# Micromouse.net
KiCad netlist of a schematic drawn in Altium Designer
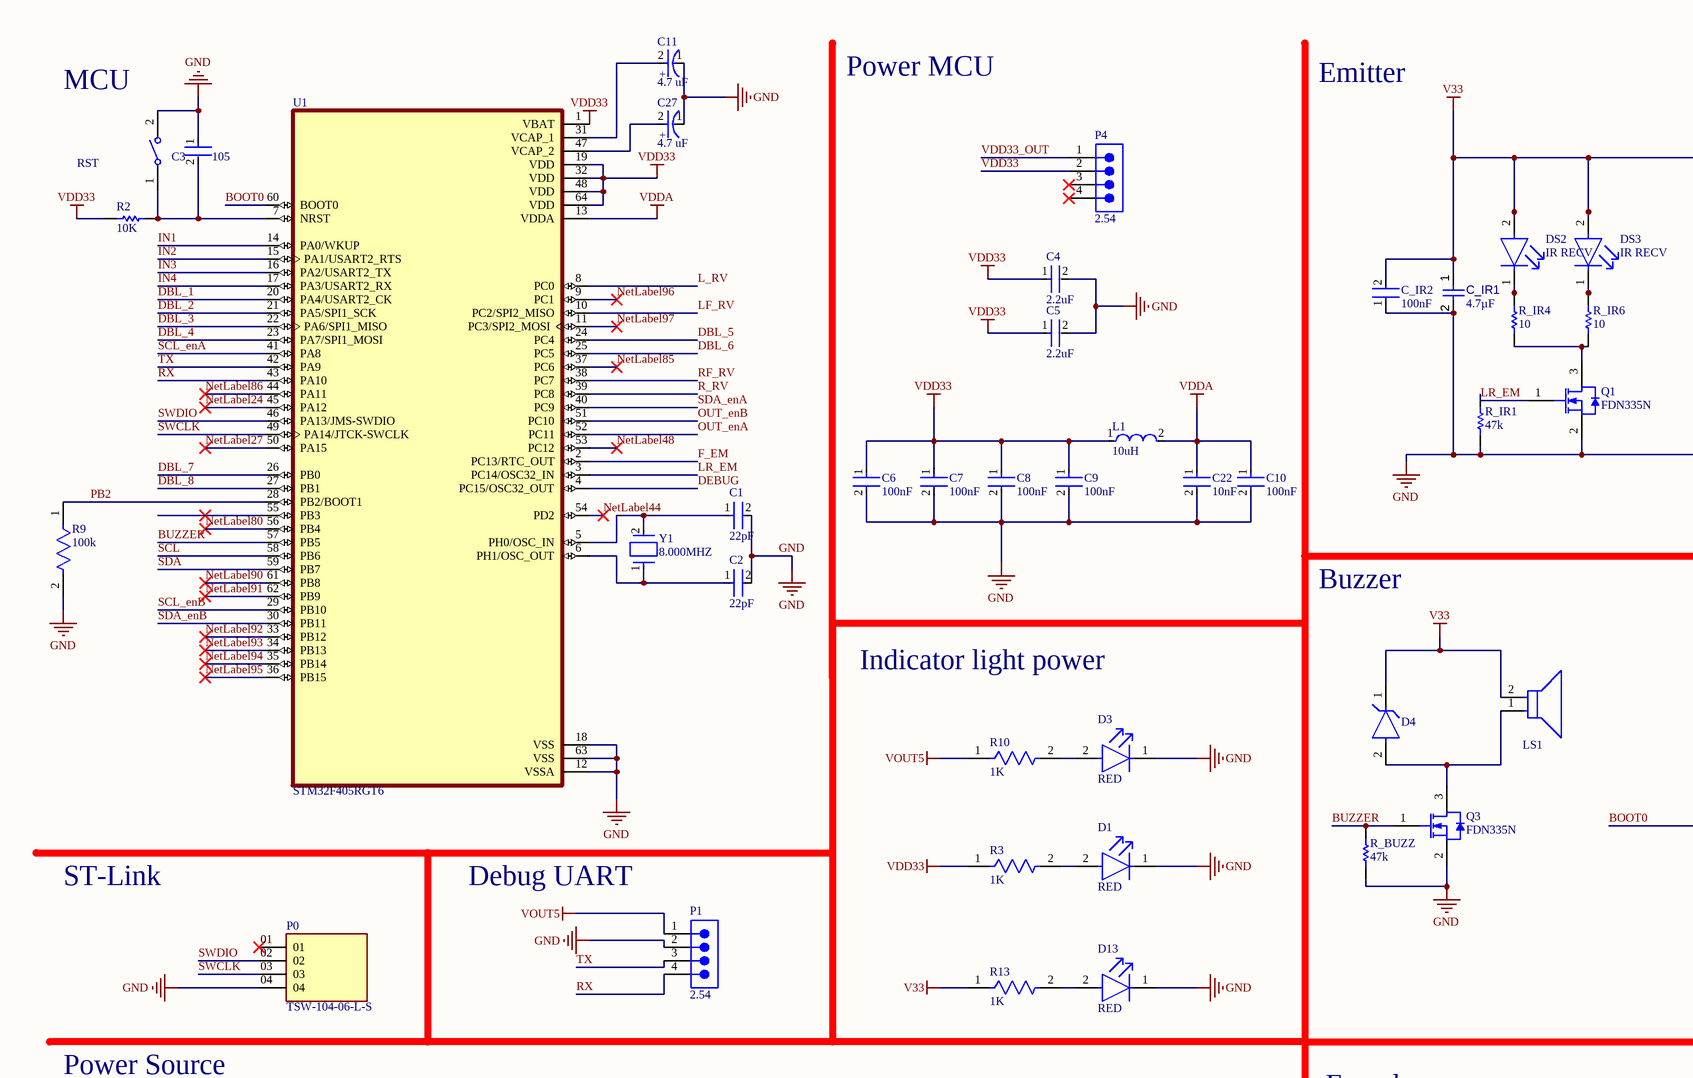
[diagram p0: Micromouse.SchDoc, top left]
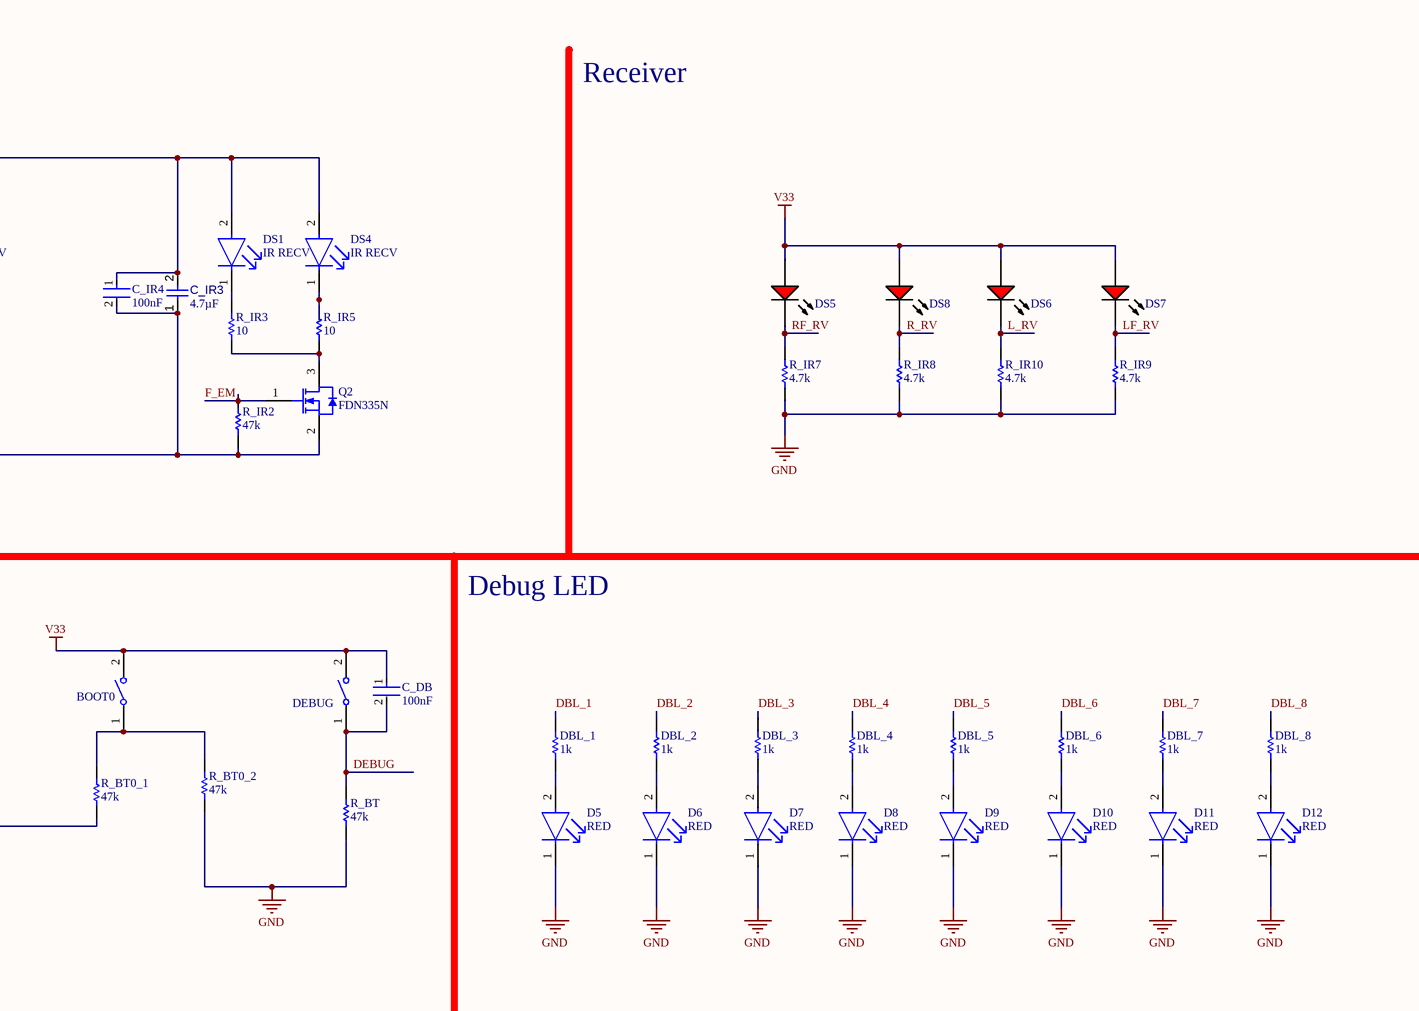
[diagram p1: Micromouse.SchDoc, top right]
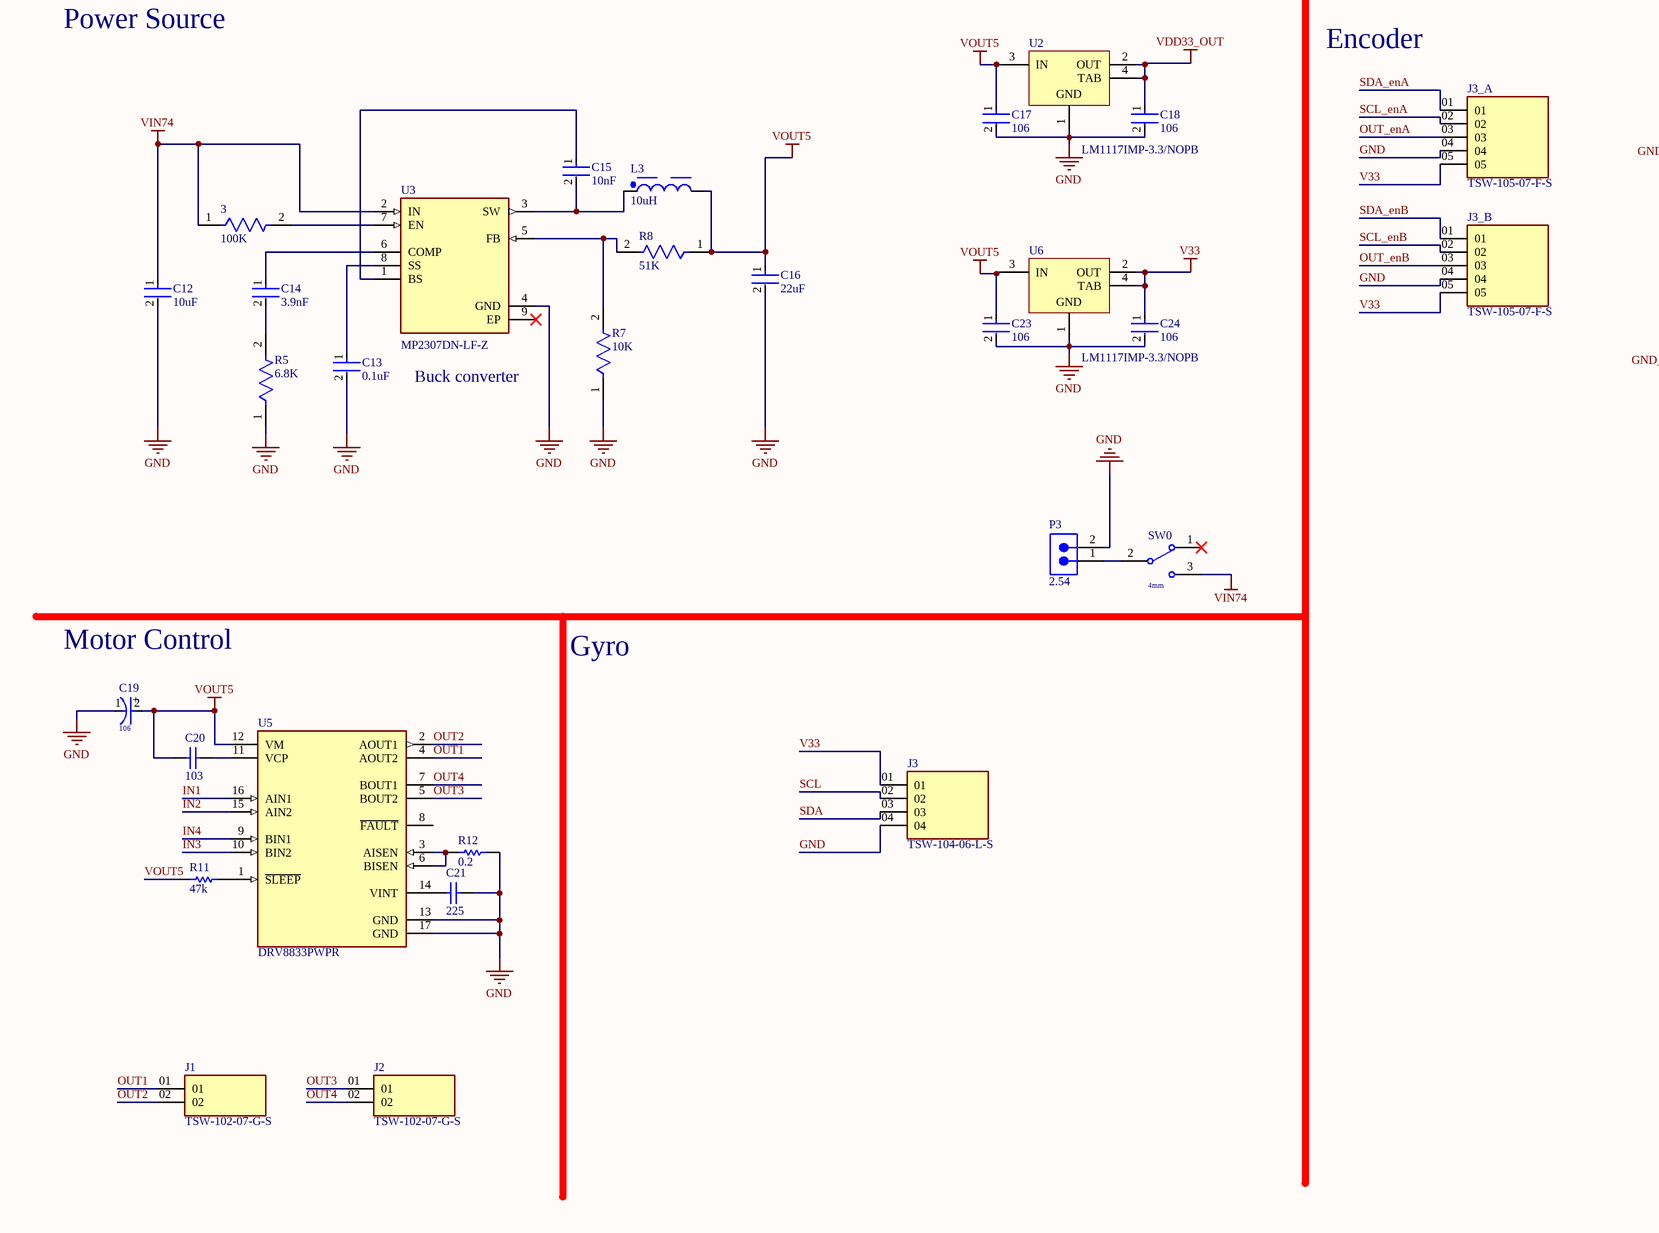
[diagram p2: Micromouse.SchDoc, bottom left]
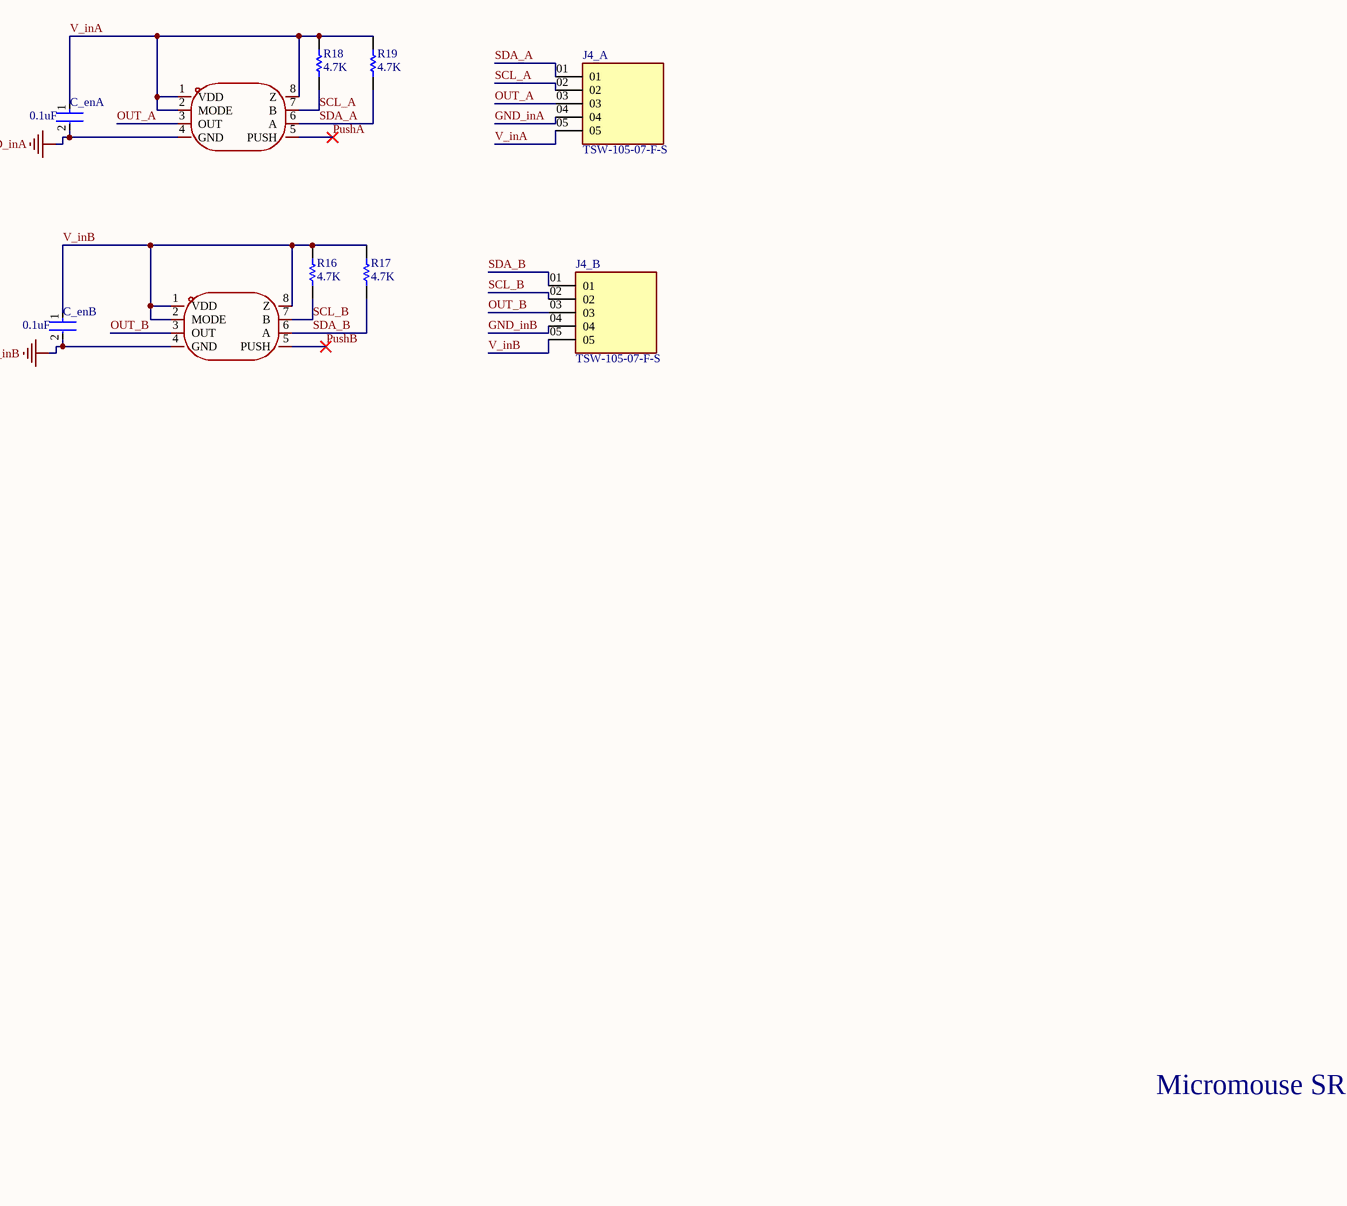
[diagram p3: Micromouse.SchDoc, bottom right]

(export (version "E")
  (design (tool "Eeschema 10.0.6"))
  (components
    (comp (ref "3")
      (value "100K")
      (footprint "FP-CRCW0805-e3-IPC_B")
      (description "RES Thick Film, 2.49Ω, 1%, 0.125W, 200ppm/°C, 0805")
      (fields (field (name "TOLERANCE") "1%"))
      (libsource (lib "Altium Content Vault") (part "1029c3af85768c4190bb7ad29bc67b5"))
    )
    (comp (ref "BOOT0")
      (value "~")
      (footprint "TECO-FSMSMTR_V")
      (description "FSMSM Push Button Switch, 50 mA, -35 to 85 degC, 2-Pin SMD, RoHS, Tape and Reel")
      (fields (field (name "MANUFACTURER") "TE Connectivity"))
      (libsource (lib "Altium Content Vault") (part "SW-SPST-2_C"))
    )
    (comp (ref "C1")
      (value "22pF")
      (footprint "FP-CL32-IPC_B")
      (description "Cap Ceramic 22uF 6.3V X7R ±20% SMD 1210 +125°C Embossed T/R")
      (fields (field (name "TOLERANCE") "20%"))
      (libsource (lib "Altium Content Vault") (part "b4654b650e69147ec39a6b967a45e02"))
    )
    (comp (ref "C2")
      (value "22pF")
      (footprint "FP-CL32-IPC_B")
      (description "Cap Ceramic 22uF 6.3V X7R ±20% SMD 1210 +125°C Embossed T/R")
      (fields (field (name "TOLERANCE") "20%"))
      (libsource (lib "Altium Content Vault") (part "b4654b650e69147ec39a6b967a45e02"))
    )
    (comp (ref "C3")
      (value "105")
      (footprint "FP-CL21-IPC_B")
      (description "CL21 Series 0805 1uF 25V -20/+80% Tolerance Y5V Multilayer Ceramic Chip Capacitor")
      (fields (field (name "TOLERANCE") "80%"))
      (libsource (lib "Altium Content Vault") (part "b4654b650e69147ec39a6b967a45e02"))
    )
    (comp (ref "C4")
      (value "2.2uF")
      (footprint "FP-CL21-IPC_B")
      (description "CL21 Series 0805 2.2uF 16V -20/+80% Tolerance Y5V Multilayer Ceramic Chip Capacitor")
      (fields (field (name "TOLERANCE") "80%") (field (name "VOLTAGE") "10V"))
      (libsource (lib "Altium Content Vault") (part "b4654b650e69147ec39a6b967a45e02"))
    )
    (comp (ref "C5")
      (value "2.2uF")
      (footprint "FP-CL21-IPC_B")
      (description "CL21 Series 0805 2.2uF 16V -20/+80% Tolerance Y5V Multilayer Ceramic Chip Capacitor")
      (fields (field (name "TOLERANCE") "80%") (field (name "VOLTAGE") "10V"))
      (libsource (lib "Altium Content Vault") (part "b4654b650e69147ec39a6b967a45e02"))
    )
    (comp (ref "C6")
      (value "100nF")
      (footprint "FP-CL10-IPC_C")
      (description "Cap Ceramic 100nF 25V X7R ±10% Pad SMD 0603 +125°C T/R")
      (fields (field (name "TOLERANCE") "10%"))
      (libsource (lib "Altium Content Vault") (part "b4654b650e69147ec39a6b967a45e02"))
    )
    (comp (ref "C7")
      (value "100nF")
      (footprint "FP-CL10-IPC_C")
      (description "Cap Ceramic 100nF 25V X7R ±10% Pad SMD 0603 +125°C T/R")
      (fields (field (name "TOLERANCE") "10%"))
      (libsource (lib "Altium Content Vault") (part "b4654b650e69147ec39a6b967a45e02"))
    )
    (comp (ref "C8")
      (value "100nF")
      (footprint "FP-CL10-IPC_C")
      (description "Cap Ceramic 100nF 25V X7R ±10% Pad SMD 0603 +125°C T/R")
      (fields (field (name "TOLERANCE") "10%"))
      (libsource (lib "Altium Content Vault") (part "b4654b650e69147ec39a6b967a45e02"))
    )
    (comp (ref "C9")
      (value "100nF")
      (footprint "FP-CL10-IPC_C")
      (description "Cap Ceramic 100nF 25V X7R ±10% Pad SMD 0603 +125°C T/R")
      (fields (field (name "TOLERANCE") "10%"))
      (libsource (lib "Altium Content Vault") (part "b4654b650e69147ec39a6b967a45e02"))
    )
    (comp (ref "C10")
      (value "100nF")
      (footprint "FP-CL10-IPC_C")
      (description "Cap Ceramic 100nF 25V X7R ±10% Pad SMD 0603 +125°C T/R")
      (fields (field (name "TOLERANCE") "10%"))
      (libsource (lib "Altium Content Vault") (part "b4654b650e69147ec39a6b967a45e02"))
    )
    (comp (ref "C11")
      (value "4.7 uF")
      (footprint "FP-TAJA-MFG")
      (description "4.7uF 20V  ±10% 4Ω 3216(mm)  SMD Tantalum Capacitor")
      (fields (field (name "TOLERANCE") "10%") (field (name "VOLTAGE") "20V"))
      (libsource (lib "Altium Content Vault") (part "203bc49f2ac43e59fd269a8c329ed05"))
    )
    (comp (ref "C12")
      (value "10uF")
      (footprint "FP-C1206C-EB-MFG")
      (description "C1206 10 uF C0G 5.00% 50 V")
      (fields
        (field (name "MANUFACTURER PART NUMBER") "C1206C100J5GAC")
        (field (name "MANUFACTURER") "KEMET")
      )
      (libsource (lib "Altium Content Vault") (part "b4654b650e69147ec39a6b967a45e02"))
    )
    (comp (ref "C13")
      (value "0.1uF")
      (footprint "FP-C1206C-EB-MFG")
      (description "C1206 10 pF C0G 5.00% 50 V")
      (fields
        (field (name "MANUFACTURER PART NUMBER") "C1206C100J5GAC")
        (field (name "MANUFACTURER") "KEMET")
      )
      (libsource (lib "Altium Content Vault") (part "b4654b650e69147ec39a6b967a45e02"))
    )
    (comp (ref "C14")
      (value "3.9nF")
      (footprint "FP-C1206C-EB-MFG")
      (description "C1206 4.8nF C0G 5.00% 50 V")
      (fields
        (field (name "MANUFACTURER PART NUMBER") "C1206C100J5GAC")
        (field (name "MANUFACTURER") "KEMET")
      )
      (libsource (lib "Altium Content Vault") (part "b4654b650e69147ec39a6b967a45e02"))
    )
    (comp (ref "C15")
      (value "10nF")
      (footprint "FP-C1206C-EB-MFG")
      (description "C1206 10 pF C0G 5.00% 50 V")
      (fields
        (field (name "MANUFACTURER PART NUMBER") "C1206C100J5GAC")
        (field (name "MANUFACTURER") "KEMET")
      )
      (libsource (lib "Altium Content Vault") (part "b4654b650e69147ec39a6b967a45e02"))
    )
    (comp (ref "C16")
      (value "22uF")
      (footprint "FP-C1206C-EB-MFG")
      (description "C1206 10 pF C0G 5.00% 50 V")
      (fields
        (field (name "MANUFACTURER PART NUMBER") "C1206C100J5GAC")
        (field (name "MANUFACTURER") "KEMET")
      )
      (libsource (lib "Altium Content Vault") (part "b4654b650e69147ec39a6b967a45e02"))
    )
    (comp (ref "C17")
      (value "106")
      (footprint "FP-GRT31C-0_2-IPC_A")
      (description "Multi-Layer Ceramic Capacitor 10uF 50V X5R ±10% 1206 Emboss T/R")
      (fields (field (name "TOLERANCE") "10%"))
      (libsource (lib "Altium Content Vault") (part "02cd4be3c70576c341d710602a673aa"))
    )
    (comp (ref "C18")
      (value "106")
      (footprint "FP-GRT31C-0_2-IPC_A")
      (description "Multi-Layer Ceramic Capacitor 10uF 50V X5R ±10% 1206 Emboss T/R")
      (fields (field (name "TOLERANCE") "10%"))
      (libsource (lib "Altium Content Vault") (part "02cd4be3c70576c341d710602a673aa"))
    )
    (comp (ref "C19")
      (value "106")
      (footprint "FP-T491C-MFG")
      (description "CAP TANT 10UF 10% 25V 2312")
      (fields (field (name "TOLERANCE") "10%") (field (name "MANUFACTURER PART NUMBER") "T491C106K025AT"))
      (libsource (lib "Altium Content Vault") (part "203bc49f2ac43e59fd269a8c329ed05"))
    )
    (comp (ref "C20")
      (value "103")
      (footprint "CAPC2013X88X50LL20T25")
      (fields (field (name "MANUFACTURER") "Kemet") (field (name "PART NUMBER") "C0805C103K5RACTU"))
      (libsource (lib "Altium Content Vault") (part "CAP"))
    )
    (comp (ref "C21")
      (value "225")
      (footprint "CAPC3216X180X50LL20T25")
      (description "Chip Capacitor, 2.2 uF, +/- 10%, 50 V, -55 to 125 degC, 1206 (3216 Metric), RoHS, Tape and Reel")
      (fields (field (name "MANUFACTURER") "Kemet") (field (name "TOLERANCE") "10%"))
      (libsource (lib "Altium Content Vault") (part "CAP-NP-2"))
    )
    (comp (ref "C22")
      (value "10nF")
      (footprint "FP-CL10-IPC_C")
      (description "Cap Ceramic 100nF 25V X7R ±10% Pad SMD 0603 +125°C T/R")
      (fields (field (name "TOLERANCE") "10%"))
      (libsource (lib "Altium Content Vault") (part "b4654b650e69147ec39a6b967a45e02"))
    )
    (comp (ref "C23")
      (value "106")
      (footprint "FP-GRT31C-0_2-IPC_A")
      (description "Multi-Layer Ceramic Capacitor 10uF 50V X5R ±10% 1206 Emboss T/R")
      (fields (field (name "TOLERANCE") "10%"))
      (libsource (lib "Altium Content Vault") (part "02cd4be3c70576c341d710602a673aa"))
    )
    (comp (ref "C24")
      (value "106")
      (footprint "FP-GRT31C-0_2-IPC_A")
      (description "Multi-Layer Ceramic Capacitor 10uF 50V X5R ±10% 1206 Emboss T/R")
      (fields (field (name "TOLERANCE") "10%"))
      (libsource (lib "Altium Content Vault") (part "02cd4be3c70576c341d710602a673aa"))
    )
    (comp (ref "C27")
      (value "4.7 uF")
      (footprint "FP-TAJA-MFG")
      (description "4.7uF 20V  ±10% 4Ω 3216(mm)  SMD Tantalum Capacitor")
      (fields (field (name "TOLERANCE") "10%") (field (name "VOLTAGE") "20V"))
      (libsource (lib "Altium Content Vault") (part "203bc49f2ac43e59fd269a8c329ed05"))
    )
    (comp (ref "C_DB")
      (value "100nF")
      (footprint "FP-CL10-IPC_C")
      (description "Cap Ceramic 100nF 25V X7R ±10% Pad SMD 0603 +125°C T/R")
      (fields (field (name "TOLERANCE") "10%"))
      (libsource (lib "Altium Content Vault") (part "b4654b650e69147ec39a6b967a45e02"))
    )
    (comp (ref "C_enA")
      (value "0.1uF")
      (footprint "FP-C1206C-EB-MFG")
      (description "C1206 10 pF C0G 5.00% 50 V")
      (fields
        (field (name "MANUFACTURER PART NUMBER") "C1206C100J5GAC")
        (field (name "MANUFACTURER") "KEMET")
      )
      (libsource (lib "Altium Content Vault") (part "b4654b650e69147ec39a6b967a45e02"))
    )
    (comp (ref "C_enB")
      (value "0.1uF")
      (footprint "FP-C1206C-EB-MFG")
      (description "C1206 10 pF C0G 5.00% 50 V")
      (fields
        (field (name "MANUFACTURER PART NUMBER") "C1206C100J5GAC")
        (field (name "MANUFACTURER") "KEMET")
      )
      (libsource (lib "Altium Content Vault") (part "b4654b650e69147ec39a6b967a45e02"))
    )
    (comp (ref "C_IR1")
      (value "4.7µF")
      (footprint "CAPC0805(2012)145_L")
      (description "Chip Capacitor, 4.7µF +/-40%, 25V, 0805, Thickness 1.45 mm")
      (fields (field (name "TOLERANCE") "20%") (field (name "Comment") "Capacitor 4.7µF +/-40% 25V 0805"))
      (libsource (lib "Nguyen Hai Son") (part "CAP-NP-2"))
    )
    (comp (ref "C_IR2")
      (value "100nF")
      (footprint "FP-CL10-IPC_C")
      (description "Cap Ceramic 100nF 25V X7R ±10% Pad SMD 0603 +125°C T/R")
      (fields (field (name "TOLERANCE") "10%"))
      (libsource (lib "Altium Content Vault") (part "b4654b650e69147ec39a6b967a45e02"))
    )
    (comp (ref "C_IR3")
      (value "4.7µF")
      (footprint "CAPC0805(2012)145_L")
      (description "Chip Capacitor, 4.7µF +/-40%, 25V, 0805, Thickness 1.45 mm")
      (fields (field (name "TOLERANCE") "20%") (field (name "Comment") "Capacitor 4.7µF +/-40% 25V 0805"))
      (libsource (lib "Nguyen Hai Son") (part "CAP-NP-2"))
    )
    (comp (ref "C_IR4")
      (value "100nF")
      (footprint "FP-CL10-IPC_C")
      (description "Cap Ceramic 100nF 25V X7R ±10% Pad SMD 0603 +125°C T/R")
      (fields (field (name "TOLERANCE") "10%"))
      (libsource (lib "Altium Content Vault") (part "b4654b650e69147ec39a6b967a45e02"))
    )
    (comp (ref "D1")
      (value "RED")
      (footprint "FP-LTST-C190GKT-MFG")
      (description "LED GREEN CLEAR CHIP SMD")
      (fields (field (name "VOLTAGE") "2V"))
      (libsource (lib "Altium Content Vault") (part "8706943c75ba83719d021d2fdc84c58"))
    )
    (comp (ref "D3")
      (value "RED")
      (footprint "FP-LTST-C190GKT-MFG")
      (description "LED GREEN CLEAR CHIP SMD")
      (fields (field (name "VOLTAGE") "2V"))
      (libsource (lib "Altium Content Vault") (part "8706943c75ba83719d021d2fdc84c58"))
    )
    (comp (ref "D4")
      (value "MMSZ5232B")
      (footprint "FP-MA02A-MFG")
      (description "MMSZ5232B MMSZ523 Series 500 mW 5.6 V 10 mA SMT Half-Watt Zener Diode SOD-123")
      (fields (field (name "TOLERANCE") "5%"))
      (libsource (lib "Altium Content Vault") (part "f813f71cba58e380607f5dd3caf9714"))
    )
    (comp (ref "D5")
      (value "RED")
      (footprint "FP-LTST-C190GKT-MFG")
      (description "LED GREEN CLEAR CHIP SMD")
      (fields (field (name "VOLTAGE") "2V"))
      (libsource (lib "Altium Content Vault") (part "8706943c75ba83719d021d2fdc84c58"))
    )
    (comp (ref "D6")
      (value "RED")
      (footprint "FP-LTST-C190GKT-MFG")
      (description "LED GREEN CLEAR CHIP SMD")
      (fields (field (name "VOLTAGE") "2V"))
      (libsource (lib "Altium Content Vault") (part "8706943c75ba83719d021d2fdc84c58"))
    )
    (comp (ref "D7")
      (value "RED")
      (footprint "FP-LTST-C190GKT-MFG")
      (description "LED GREEN CLEAR CHIP SMD")
      (fields (field (name "VOLTAGE") "2V"))
      (libsource (lib "Altium Content Vault") (part "8706943c75ba83719d021d2fdc84c58"))
    )
    (comp (ref "D8")
      (value "RED")
      (footprint "FP-LTST-C190GKT-MFG")
      (description "LED GREEN CLEAR CHIP SMD")
      (fields (field (name "VOLTAGE") "2V"))
      (libsource (lib "Altium Content Vault") (part "8706943c75ba83719d021d2fdc84c58"))
    )
    (comp (ref "D9")
      (value "RED")
      (footprint "FP-LTST-C190GKT-MFG")
      (description "LED GREEN CLEAR CHIP SMD")
      (fields (field (name "VOLTAGE") "2V"))
      (libsource (lib "Altium Content Vault") (part "8706943c75ba83719d021d2fdc84c58"))
    )
    (comp (ref "D10")
      (value "RED")
      (footprint "FP-LTST-C190GKT-MFG")
      (description "LED GREEN CLEAR CHIP SMD")
      (fields (field (name "VOLTAGE") "2V"))
      (libsource (lib "Altium Content Vault") (part "8706943c75ba83719d021d2fdc84c58"))
    )
    (comp (ref "D11")
      (value "RED")
      (footprint "FP-LTST-C190GKT-MFG")
      (description "LED GREEN CLEAR CHIP SMD")
      (fields (field (name "VOLTAGE") "2V"))
      (libsource (lib "Altium Content Vault") (part "8706943c75ba83719d021d2fdc84c58"))
    )
    (comp (ref "D12")
      (value "RED")
      (footprint "FP-LTST-C190GKT-MFG")
      (description "LED GREEN CLEAR CHIP SMD")
      (fields (field (name "VOLTAGE") "2V"))
      (libsource (lib "Altium Content Vault") (part "8706943c75ba83719d021d2fdc84c58"))
    )
    (comp (ref "D13")
      (value "RED")
      (footprint "FP-LTST-C190GKT-MFG")
      (description "LED GREEN CLEAR CHIP SMD")
      (fields (field (name "VOLTAGE") "2V"))
      (libsource (lib "Altium Content Vault") (part "8706943c75ba83719d021d2fdc84c58"))
    )
    (comp (ref "DBL_1")
      (value "1k")
      (footprint "RESC2013X70X40ML20T20")
      (description "Chip Resistor, 1 KOhm, +/- 1%, 0.125 W, -55 to 155 degC, 0805 (2013 Metric)")
      (fields (field (name "TOLERANCE") "1%") (field (name "POWER") "125mW"))
      (libsource (lib "Nguyen Hai Son") (part "RES-2"))
    )
    (comp (ref "DBL_2")
      (value "1k")
      (footprint "RESC2013X70X40ML20T20")
      (description "Chip Resistor, 1 KOhm, +/- 1%, 0.125 W, -55 to 155 degC, 0805 (2013 Metric)")
      (fields (field (name "TOLERANCE") "1%") (field (name "POWER") "125mW"))
      (libsource (lib "Nguyen Hai Son") (part "RES-2"))
    )
    (comp (ref "DBL_3")
      (value "1k")
      (footprint "RESC2013X70X40ML20T20")
      (description "Chip Resistor, 1 KOhm, +/- 1%, 0.125 W, -55 to 155 degC, 0805 (2013 Metric)")
      (fields (field (name "TOLERANCE") "1%") (field (name "POWER") "125mW"))
      (libsource (lib "Nguyen Hai Son") (part "RES-2"))
    )
    (comp (ref "DBL_4")
      (value "1k")
      (footprint "RESC2013X70X40ML20T20")
      (description "Chip Resistor, 1 KOhm, +/- 1%, 0.125 W, -55 to 155 degC, 0805 (2013 Metric)")
      (fields (field (name "TOLERANCE") "1%") (field (name "POWER") "125mW"))
      (libsource (lib "Nguyen Hai Son") (part "RES-2"))
    )
    (comp (ref "DBL_5")
      (value "1k")
      (footprint "RESC2013X70X40ML20T20")
      (description "Chip Resistor, 1 KOhm, +/- 1%, 0.125 W, -55 to 155 degC, 0805 (2013 Metric)")
      (fields (field (name "TOLERANCE") "1%") (field (name "POWER") "125mW"))
      (libsource (lib "Nguyen Hai Son") (part "RES-2"))
    )
    (comp (ref "DBL_6")
      (value "1k")
      (footprint "RESC2013X70X40ML20T20")
      (description "Chip Resistor, 1 KOhm, +/- 1%, 0.125 W, -55 to 155 degC, 0805 (2013 Metric)")
      (fields (field (name "TOLERANCE") "1%") (field (name "POWER") "125mW"))
      (libsource (lib "Nguyen Hai Son") (part "RES-2"))
    )
    (comp (ref "DBL_7")
      (value "1k")
      (footprint "RESC2013X70X40ML20T20")
      (description "Chip Resistor, 1 KOhm, +/- 1%, 0.125 W, -55 to 155 degC, 0805 (2013 Metric)")
      (fields (field (name "TOLERANCE") "1%") (field (name "POWER") "125mW"))
      (libsource (lib "Nguyen Hai Son") (part "RES-2"))
    )
    (comp (ref "DBL_8")
      (value "1k")
      (footprint "RESC2013X70X40ML20T20")
      (description "Chip Resistor, 1 KOhm, +/- 1%, 0.125 W, -55 to 155 degC, 0805 (2013 Metric)")
      (fields (field (name "TOLERANCE") "1%") (field (name "POWER") "125mW"))
      (libsource (lib "Nguyen Hai Son") (part "RES-2"))
    )
    (comp (ref "DEBUG")
      (value "~")
      (footprint "TECO-FSMSMTR_V")
      (description "FSMSM Push Button Switch, 50 mA, -35 to 85 degC, 2-Pin SMD, RoHS, Tape and Reel")
      (fields (field (name "MANUFACTURER") "TE Connectivity"))
      (libsource (lib "Altium Content Vault") (part "SW-SPST-2_C"))
    )
    (comp (ref "DS1")
      (value "IR RECV")
      (footprint "FP-6_544-5258_09-4-MFG")
      (description "TSFF5210 TSFF5210 IR LED, 870nm, T-1 3/4 (5mm) Through Hole package")
      (libsource (lib "Altium Content Vault") (part "8706943c75ba83719d021d2fdc84c58"))
    )
    (comp (ref "DS2")
      (value "IR RECV")
      (footprint "FP-6_544-5258_09-4-MFG")
      (description "TSFF5210 TSFF5210 IR LED, 870nm, T-1 3/4 (5mm) Through Hole package")
      (libsource (lib "Altium Content Vault") (part "8706943c75ba83719d021d2fdc84c58"))
    )
    (comp (ref "DS3")
      (value "IR RECV")
      (footprint "FP-6_544-5258_09-4-MFG")
      (description "TSFF5210 TSFF5210 IR LED, 870nm, T-1 3/4 (5mm) Through Hole package")
      (libsource (lib "Altium Content Vault") (part "8706943c75ba83719d021d2fdc84c58"))
    )
    (comp (ref "DS4")
      (value "IR RECV")
      (footprint "FP-6_544-5258_09-4-MFG")
      (description "TSFF5210 TSFF5210 IR LED, 870nm, T-1 3/4 (5mm) Through Hole package")
      (libsource (lib "Altium Content Vault") (part "8706943c75ba83719d021d2fdc84c58"))
    )
    (comp (ref "DS5")
      (value "UR502DC")
      (footprint "CGX-UR502DC")
      (description "Red LED, 80 mW, 30 mA, -25 to 85 degC, 2-Pin THD")
      (fields (field (name "POWER") "80mW") (field (name "MANUFACTURER") "Shenzhen CGX"))
      (libsource (lib "Nguyen Hai Son") (part "LED-RED-AK-2"))
    )
    (comp (ref "DS6")
      (value "UR502DC")
      (footprint "CGX-UR502DC")
      (description "Red LED, 80 mW, 30 mA, -25 to 85 degC, 2-Pin THD")
      (fields (field (name "POWER") "80mW") (field (name "MANUFACTURER") "Shenzhen CGX"))
      (libsource (lib "Nguyen Hai Son") (part "LED-RED-AK-2"))
    )
    (comp (ref "DS7")
      (value "UR502DC")
      (footprint "CGX-UR502DC")
      (description "Red LED, 80 mW, 30 mA, -25 to 85 degC, 2-Pin THD")
      (fields (field (name "POWER") "80mW") (field (name "MANUFACTURER") "Shenzhen CGX"))
      (libsource (lib "Nguyen Hai Son") (part "LED-RED-AK-2"))
    )
    (comp (ref "DS8")
      (value "UR502DC")
      (footprint "CGX-UR502DC")
      (description "Red LED, 80 mW, 30 mA, -25 to 85 degC, 2-Pin THD")
      (fields (field (name "POWER") "80mW") (field (name "MANUFACTURER") "Shenzhen CGX"))
      (libsource (lib "Nguyen Hai Son") (part "LED-RED-AK-2"))
    )
    (comp (ref "J1")
      (value "TSW-102-07-G-S")
      (footprint "SAMTEC_TSW-102-07-G-S")
      (fields (field (name "MF") "Samtec"))
      (libsource (lib "Nguyen Hai Son") (part "TSW-102-07-G-S"))
    )
    (comp (ref "J2")
      (value "TSW-102-07-G-S")
      (footprint "SAMTEC_TSW-102-07-G-S")
      (fields (field (name "MF") "Samtec"))
      (libsource (lib "Nguyen Hai Son") (part "TSW-102-07-G-S"))
    )
    (comp (ref "J3")
      (value "TSW-104-06-L-S")
      (footprint "SAMTEC_TSW-104-06-L-S")
      (libsource (lib "Vũ Hiệp") (part "TSW-104-06-L-S"))
    )
    (comp (ref "J3_A")
      (value "TSW-105-07-F-S")
      (footprint "SAMTEC_TSW-105-07-F-S")
      (fields (field (name "MF") "Samtec"))
      (libsource (lib "Vũ Hiệp") (part "TSW-105-07-F-S"))
    )
    (comp (ref "J3_B")
      (value "TSW-105-07-F-S")
      (footprint "SAMTEC_TSW-105-07-F-S")
      (fields (field (name "MF") "Samtec"))
      (libsource (lib "Vũ Hiệp") (part "TSW-105-07-F-S"))
    )
    (comp (ref "J4_A")
      (value "TSW-105-07-F-S")
      (footprint "SAMTEC_TSW-105-07-F-S")
      (fields (field (name "MF") "Samtec"))
      (libsource (lib "Vũ Hiệp") (part "TSW-105-07-F-S"))
    )
    (comp (ref "J4_B")
      (value "TSW-105-07-F-S")
      (footprint "SAMTEC_TSW-105-07-F-S")
      (fields (field (name "MF") "Samtec"))
      (libsource (lib "Vũ Hiệp") (part "TSW-105-07-F-S"))
    )
    (comp (ref "L1")
      (value "10uH")
      (footprint "FP-CB2012-IPC_C")
      (description "SMD Inductors 10uH ±20% 0.34A 1.56Ω 0805")
      (fields (field (name "TOLERANCE") "20%"))
      (libsource (lib "Altium Content Vault") (part "725321dda6339637d4d059423bc1c3c"))
    )
    (comp (ref "L3")
      (value "10uH")
      (footprint "WE-TPC_5818")
      (fields (field (name "TOLERANCE") "30%"))
      (libsource (lib "Altium Content Vault") (part "Inductor - 2"))
    )
    (comp (ref "LS1")
      (value "MCKPX-G1203A-K4056")
      (footprint "FP-MCKPX-G1203A-K4056-MFG")
      (description "MAGNETIC BUZZER AND TRANSDUCER - More Details")
      (fields
        (field (name "MANUFACTURER") "Multicomp Pro")
        (field (name "OCTOPART") "https://octopart.com/mckpx-g1203a-k4056-multicomp-12157154")
      )
      (libsource (lib "Altium Content Vault") (part "1973c4b650225fd2ddacaff6b763965"))
    )
    (comp (ref "P0")
      (value "TSW-104-06-L-S")
      (footprint "SAMTEC_TSW-104-06-L-S")
      (libsource (lib "Vũ Hiệp") (part "TSW-104-06-L-S"))
    )
    (comp (ref "P1")
      (value "2.54")
      (footprint "61300411121")
      (libsource (lib "Altium Content Vault") (part "Header_Male_1R_04P"))
    )
    (comp (ref "P3")
      (value "2.54")
      (footprint "61300211121")
      (libsource (lib "Altium Content Vault") (part "Header_Male_1R_02P"))
    )
    (comp (ref "P4")
      (value "2.54")
      (footprint "61300411121")
      (libsource (lib "Altium Content Vault") (part "Header_Male_1R_04P"))
    )
    (comp (ref "Q1")
      (value "FDN335N")
      (footprint "FAIR-SSOT3L-3_V")
      (fields (field (name "MANUFACTURER") "FairchildSemiconductor"))
      (libsource (lib "Altium Content Vault") (part "NEMOS-GSD-3"))
    )
    (comp (ref "Q2")
      (value "FDN335N")
      (footprint "FAIR-SSOT3L-3_V")
      (fields (field (name "MANUFACTURER") "FairchildSemiconductor"))
      (libsource (lib "Altium Content Vault") (part "NEMOS-GSD-3"))
    )
    (comp (ref "Q3")
      (value "FDN335N")
      (footprint "FAIR-SSOT3L-3_V")
      (fields (field (name "MANUFACTURER") "FairchildSemiconductor"))
      (libsource (lib "Altium Content Vault") (part "NEMOS-GSD-3"))
    )
    (comp (ref "R2")
      (value "10K")
      (footprint "RESC1206(3216)_M")
      (description "10K 0.25W 5% 1206 (3216 Metric)  SMD")
      (fields (field (name "POWER") "0.25 W") (field (name "TOLERANCE") "5 %"))
      (libsource (lib "Altium Content Vault") (part "RES"))
    )
    (comp (ref "R3")
      (value "1K")
      (footprint "FP-RC1005-IPC_A")
      (description "Res Thick Film 0402 1kΩ 1% 0.063W ±100ppm/°C Molded SMD T/R")
      (fields (field (name "TOLERANCE") "1%"))
      (libsource (lib "Altium Content Vault") (part "1029c3af85768c4190bb7ad29bc67b5"))
    )
    (comp (ref "R5")
      (value "6.8K")
      (footprint "FP-CRCW0805-e3-IPC_B")
      (description "RES Thick Film, 2.49Ω, 1%, 0.125W, 200ppm/°C, 0805")
      (fields (field (name "TOLERANCE") "1%"))
      (libsource (lib "Altium Content Vault") (part "1029c3af85768c4190bb7ad29bc67b5"))
    )
    (comp (ref "R7")
      (value "10K")
      (footprint "FP-CRCW0805-e3-IPC_B")
      (description "RES Thick Film, 2.49Ω, 1%, 0.125W, 200ppm/°C, 0805")
      (fields (field (name "TOLERANCE") "1%"))
      (libsource (lib "Altium Content Vault") (part "1029c3af85768c4190bb7ad29bc67b5"))
    )
    (comp (ref "R8")
      (value "51K")
      (footprint "FP-CRCW0805-e3-IPC_B")
      (description "RES Thick Film, 2.49Ω, 1%, 0.125W, 200ppm/°C, 0805")
      (fields (field (name "TOLERANCE") "1%"))
      (libsource (lib "Altium Content Vault") (part "1029c3af85768c4190bb7ad29bc67b5"))
    )
    (comp (ref "R9")
      (value "100k")
      (footprint "FP-RC3216-IPC_C")
      (description "Res Thick Film 1206 10kΩ 5% 0.25W ±100ppm/°C Molded SMD T/R")
      (fields (field (name "TOLERANCE") "5%"))
      (libsource (lib "Altium Content Vault") (part "1029c3af85768c4190bb7ad29bc67b5"))
    )
    (comp (ref "R10")
      (value "1K")
      (footprint "FP-RC1005-IPC_A")
      (description "Res Thick Film 0402 1kΩ 1% 0.063W ±100ppm/°C Molded SMD T/R")
      (fields (field (name "TOLERANCE") "1%"))
      (libsource (lib "Altium Content Vault") (part "1029c3af85768c4190bb7ad29bc67b5"))
    )
    (comp (ref "R11")
      (value "47k")
      (footprint "RESC3216X60X45LL10T20")
      (fields (field (name "PART NUMBER") "CRCW120647K0FKEA") (field (name "MANUFACTURER") "Vishay Dale"))
      (libsource (lib "Altium Content Vault") (part "RES"))
    )
    (comp (ref "R12")
      (value "0.2")
      (footprint "RESC3216X89X51ML25T25")
      (fields (field (name "MANUFACTURER") "Vishay Dale") (field (name "PART NUMBER") "WSL1206R2000FEA"))
      (libsource (lib "Altium Content Vault") (part "RES"))
    )
    (comp (ref "R13")
      (value "1K")
      (footprint "FP-RC1005-IPC_A")
      (description "Res Thick Film 0402 1kΩ 1% 0.063W ±100ppm/°C Molded SMD T/R")
      (fields (field (name "TOLERANCE") "1%"))
      (libsource (lib "Altium Content Vault") (part "1029c3af85768c4190bb7ad29bc67b5"))
    )
    (comp (ref "R16")
      (value "4.7K")
      (footprint "RESC3216X60X45LL10T20")
      (fields (field (name "PART NUMBER") "CRCW120647K0FKEA") (field (name "MANUFACTURER") "Vishay Dale"))
      (libsource (lib "Altium Content Vault") (part "RES"))
    )
    (comp (ref "R17")
      (value "4.7K")
      (footprint "RESC3216X60X45LL10T20")
      (fields (field (name "PART NUMBER") "CRCW120647K0FKEA") (field (name "MANUFACTURER") "Vishay Dale"))
      (libsource (lib "Altium Content Vault") (part "RES"))
    )
    (comp (ref "R18")
      (value "4.7K")
      (footprint "RESC3216X60X45LL10T20")
      (fields (field (name "PART NUMBER") "CRCW120647K0FKEA") (field (name "MANUFACTURER") "Vishay Dale"))
      (libsource (lib "Altium Content Vault") (part "RES"))
    )
    (comp (ref "R19")
      (value "4.7K")
      (footprint "RESC3216X60X45LL10T20")
      (fields (field (name "PART NUMBER") "CRCW120647K0FKEA") (field (name "MANUFACTURER") "Vishay Dale"))
      (libsource (lib "Altium Content Vault") (part "RES"))
    )
    (comp (ref "RST")
      (value "~")
      (footprint "TECO-FSMSMTR_V")
      (description "FSMSM Push Button Switch, 50 mA, -35 to 85 degC, 2-Pin SMD, RoHS, Tape and Reel")
      (fields (field (name "MANUFACTURER") "TE Connectivity"))
      (libsource (lib "Altium Content Vault") (part "SW-SPST-2_C"))
    )
    (comp (ref "R_BT")
      (value "47k")
      (footprint "RESC2013X60X35NL10T20")
      (description "Chip Resistor, 47 KOhm, +/- 1%, 0.125 W, -55 to 155 degC, 0805 (2012 Metric), RoHS, Tape and Reel")
      (fields (field (name "MANUFACTURER") "Yageo"))
      (libsource (lib "Altium Content Vault") (part "RES-2"))
    )
    (comp (ref "R_BT0_1")
      (value "47k")
      (footprint "RESC2013X60X35NL10T20")
      (description "Chip Resistor, 47 KOhm, +/- 1%, 0.125 W, -55 to 155 degC, 0805 (2012 Metric), RoHS, Tape and Reel")
      (fields (field (name "MANUFACTURER") "Yageo"))
      (libsource (lib "Altium Content Vault") (part "RES-2"))
    )
    (comp (ref "R_BT0_2")
      (value "47k")
      (footprint "RESC2013X60X35NL10T20")
      (description "Chip Resistor, 47 KOhm, +/- 1%, 0.125 W, -55 to 155 degC, 0805 (2012 Metric), RoHS, Tape and Reel")
      (fields (field (name "MANUFACTURER") "Yageo"))
      (libsource (lib "Altium Content Vault") (part "RES-2"))
    )
    (comp (ref "R_BUZZ")
      (value "47k")
      (footprint "RESC2013X60X35NL10T20")
      (description "Chip Resistor, 47 KOhm, +/- 1%, 0.125 W, -55 to 155 degC, 0805 (2012 Metric), RoHS, Tape and Reel")
      (fields (field (name "MANUFACTURER") "Yageo"))
      (libsource (lib "Altium Content Vault") (part "RES-2"))
    )
    (comp (ref "R_IR1")
      (value "47k")
      (footprint "RESC2013X60X35NL10T20")
      (description "Chip Resistor, 47 KOhm, +/- 1%, 0.125 W, -55 to 155 degC, 0805 (2012 Metric), RoHS, Tape and Reel")
      (fields (field (name "MANUFACTURER") "Yageo"))
      (libsource (lib "Altium Content Vault") (part "RES-2"))
    )
    (comp (ref "R_IR2")
      (value "47k")
      (footprint "RESC2013X60X35NL10T20")
      (description "Chip Resistor, 47 KOhm, +/- 1%, 0.125 W, -55 to 155 degC, 0805 (2012 Metric), RoHS, Tape and Reel")
      (fields (field (name "MANUFACTURER") "Yageo"))
      (libsource (lib "Altium Content Vault") (part "RES-2"))
    )
    (comp (ref "R_IR3")
      (value "10")
      (footprint "RESC2013X50X30NL20T20")
      (fields (field (name "MANUFACTURER") "Vishay Dale") (field (name "PART NUMBER") "CRCW080510R0FKEA"))
      (libsource (lib "Altium Content Vault") (part "RES"))
    )
    (comp (ref "R_IR4")
      (value "10")
      (footprint "RESC2013X50X30NL20T20")
      (fields (field (name "MANUFACTURER") "Vishay Dale") (field (name "PART NUMBER") "CRCW080510R0FKEA"))
      (libsource (lib "Altium Content Vault") (part "RES"))
    )
    (comp (ref "R_IR5")
      (value "10")
      (footprint "RESC2013X50X30NL20T20")
      (fields (field (name "MANUFACTURER") "Vishay Dale") (field (name "PART NUMBER") "CRCW080510R0FKEA"))
      (libsource (lib "Altium Content Vault") (part "RES"))
    )
    (comp (ref "R_IR6")
      (value "10")
      (footprint "RESC2013X50X30NL20T20")
      (fields (field (name "MANUFACTURER") "Vishay Dale") (field (name "PART NUMBER") "CRCW080510R0FKEA"))
      (libsource (lib "Altium Content Vault") (part "RES"))
    )
    (comp (ref "R_IR7")
      (value "4.7k")
      (footprint "YAGO-RC0805_M")
      (fields
        (field (name "TOLERANCE") "+/- 1%")
        (field (name "PARTNUMBER") "RC0805FR-074K7L")
        (field (name "POWER") "0.125 W")
      )
      (libsource (lib "Altium Content Vault") (part "YAGO-RES-2"))
    )
    (comp (ref "R_IR8")
      (value "4.7k")
      (footprint "YAGO-RC0805_M")
      (fields
        (field (name "TOLERANCE") "+/- 1%")
        (field (name "PARTNUMBER") "RC0805FR-074K7L")
        (field (name "POWER") "0.125 W")
      )
      (libsource (lib "Altium Content Vault") (part "YAGO-RES-2"))
    )
    (comp (ref "R_IR9")
      (value "4.7k")
      (footprint "YAGO-RC0805_M")
      (fields
        (field (name "TOLERANCE") "+/- 1%")
        (field (name "PARTNUMBER") "RC0805FR-074K7L")
        (field (name "POWER") "0.125 W")
      )
      (libsource (lib "Altium Content Vault") (part "YAGO-RES-2"))
    )
    (comp (ref "R_IR10")
      (value "4.7k")
      (footprint "YAGO-RC0805_M")
      (fields
        (field (name "TOLERANCE") "+/- 1%")
        (field (name "PARTNUMBER") "RC0805FR-074K7L")
        (field (name "POWER") "0.125 W")
      )
      (libsource (lib "Altium Content Vault") (part "YAGO-RES-2"))
    )
    (comp (ref "SW0")
      (value "4mm")
      (footprint "ESWI-EG1218_V")
      (description "Slide Switch, 500 V, -20 to 70 degC, 3-Pin THD, RoHS")
      (libsource (lib "Altium Content Vault") (part "SW-SPDT-3_B"))
    )
    (comp (ref "U1")
      (value "STM32F405RGT6")
      (footprint "QFP50P1200X1200X160-64N")
      (fields (field (name "MF") "STMicroelectronics"))
      (libsource (lib "Vũ Hiệp") (part "STM32F405RGT6"))
    )
    (comp (ref "U2")
      (value "LM1117IMP-3.3/NOPB")
      (footprint "DCY0004A_N")
      (description "800mA Low-Dropout Linear Regulator, 4-pin SOT-223, Pb-Free")
      (fields (field (name "MANUFACTURER") "Texas Instruments"))
      (libsource (lib "Altium Content Vault") (part "PM-REG-LM1086-SOT4"))
    )
    (comp (ref "U3")
      (value "MP2307DN-LF-Z")
      (footprint "SOIC127P600X170-9N")
      (fields (field (name "MF") "Monolithic Power"))
      (libsource (lib "MP2307DN-LF-Z") (part "MP2307DN-LF-Z"))
    )
    (comp (ref "U5")
      (value "DRV8833PWPR")
      (footprint "FP-PWP0016C-IPC_B")
      (description "IC MOTOR DRIVER PAR 16HTSSOP")
      (libsource (lib "Altium Content Vault") (part "bca689d78e207bdabf30b9b31c2f798"))
    )
    (comp (ref "U6")
      (value "LM1117IMP-3.3/NOPB")
      (footprint "DCY0004A_N")
      (description "800mA Low-Dropout Linear Regulator, 4-pin SOT-223, Pb-Free")
      (fields (field (name "MANUFACTURER") "Texas Instruments"))
      (libsource (lib "Altium Content Vault") (part "PM-REG-LM1086-SOT4"))
    )
    (comp (ref "U_enA")
      (value "MT6701CT-STD")
      (footprint "SOP-8_L4.9-W3.9-P1.27-LS6.0-BL")
      (fields (field (name "MANUFACTURER") "MagnTek(麦歌恩)"))
      (libsource (lib "altium-import") (part "root_0_MT6701CT-STD_"))
    )
    (comp (ref "U_enB")
      (value "MT6701CT-STD")
      (footprint "SOP-8_L4.9-W3.9-P1.27-LS6.0-BL")
      (fields (field (name "MANUFACTURER") "MagnTek(麦歌恩)"))
      (libsource (lib "altium-import") (part "root_0_MT6701CT-STD_"))
    )
    (comp (ref "Y1")
      (value "8.000MHZ")
      (footprint "FP-ABLS-MFG")
      (description "CRYSTAL 8.0000MHZ 18PF SMD")
      (fields (field (name "TOLERANCE") "20ppm"))
      (libsource (lib "Altium Content Vault") (part "c23a69dc6c9e2f18f2079038eb95dd1"))
    )
  )
  (nets
    (net (code "1") (name "/BOOT0") (class "Default")
      (node (ref "R_BT0_1") (pin "1") (pinfunction "1_1") (pintype "passive"))
      (node (ref "U1") (pin "60") (pinfunction "BOOT0_60") (pintype "bidirectional"))
    )
    (net (code "2") (name "/BUZZER") (class "Default")
      (node (ref "Q3") (pin "1") (pinfunction "G_1") (pintype "passive"))
      (node (ref "R_BUZZ") (pin "2") (pinfunction "2_2") (pintype "passive"))
      (node (ref "U1") (pin "57") (pinfunction "PB5_57") (pintype "bidirectional"))
    )
    (net (code "3") (name "/DBL_1") (class "Default")
      (node (ref "DBL_1") (pin "2") (pinfunction "2_2") (pintype "passive"))
      (node (ref "U1") (pin "20") (pinfunction "PA4/USART2_CK_20") (pintype "bidirectional"))
    )
    (net (code "4") (name "/DBL_2") (class "Default")
      (node (ref "DBL_2") (pin "2") (pinfunction "2_2") (pintype "passive"))
      (node (ref "U1") (pin "21") (pinfunction "PA5/SPI1_SCK_21") (pintype "bidirectional"))
    )
    (net (code "5") (name "/DBL_3") (class "Default")
      (node (ref "DBL_3") (pin "2") (pinfunction "2_2") (pintype "passive"))
      (node (ref "U1") (pin "22") (pinfunction "PA6/SPI1_MISO_22") (pintype "bidirectional"))
    )
    (net (code "6") (name "/DBL_4") (class "Default")
      (node (ref "DBL_4") (pin "2") (pinfunction "2_2") (pintype "passive"))
      (node (ref "U1") (pin "23") (pinfunction "PA7/SPI1_MOSI_23") (pintype "bidirectional"))
    )
    (net (code "7") (name "/DBL_5") (class "Default")
      (node (ref "DBL_5") (pin "2") (pinfunction "2_2") (pintype "passive"))
      (node (ref "U1") (pin "24") (pinfunction "PC4_24") (pintype "bidirectional"))
    )
    (net (code "8") (name "/DBL_6") (class "Default")
      (node (ref "DBL_6") (pin "2") (pinfunction "2_2") (pintype "passive"))
      (node (ref "U1") (pin "25") (pinfunction "PC5_25") (pintype "bidirectional"))
    )
    (net (code "9") (name "/DBL_7") (class "Default")
      (node (ref "DBL_7") (pin "2") (pinfunction "2_2") (pintype "passive"))
      (node (ref "U1") (pin "26") (pinfunction "PB0_26") (pintype "bidirectional"))
    )
    (net (code "10") (name "/DBL_8") (class "Default")
      (node (ref "DBL_8") (pin "2") (pinfunction "2_2") (pintype "passive"))
      (node (ref "U1") (pin "27") (pinfunction "PB1_27") (pintype "bidirectional"))
    )
    (net (code "11") (name "/DEBUG") (class "Default")
      (node (ref "C_DB") (pin "2") (pinfunction "2_2") (pintype "passive"))
      (node (ref "DEBUG") (pin "1") (pinfunction "1_1") (pintype "passive"))
      (node (ref "R_BT") (pin "2") (pinfunction "2_2") (pintype "passive"))
      (node (ref "U1") (pin "4") (pinfunction "PC15/OSC32_OUT_4") (pintype "bidirectional"))
    )
    (net (code "12") (name "/F_EM") (class "Default")
      (node (ref "Q2") (pin "1") (pinfunction "G_1") (pintype "passive"))
      (node (ref "R_IR2") (pin "2") (pinfunction "2_2") (pintype "passive"))
      (node (ref "U1") (pin "2") (pinfunction "PC13/RTC_OUT_2") (pintype "bidirectional"))
    )
    (net (code "13") (name "/IN1") (class "Default")
      (node (ref "U1") (pin "14") (pinfunction "PA0/WKUP_14") (pintype "bidirectional"))
      (node (ref "U5") (pin "16") (pinfunction "AIN1_16") (pintype "input"))
    )
    (net (code "14") (name "/IN2") (class "Default")
      (node (ref "U1") (pin "15") (pinfunction "PA1/USART2_RTS_15") (pintype "bidirectional"))
      (node (ref "U5") (pin "15") (pinfunction "AIN2_15") (pintype "input"))
    )
    (net (code "15") (name "/IN3") (class "Default")
      (node (ref "U1") (pin "16") (pinfunction "PA2/USART2_TX_16") (pintype "bidirectional"))
      (node (ref "U5") (pin "10") (pinfunction "BIN2_10") (pintype "input"))
    )
    (net (code "16") (name "/IN4") (class "Default")
      (node (ref "U1") (pin "17") (pinfunction "PA3/USART2_RX_17") (pintype "bidirectional"))
      (node (ref "U5") (pin "9") (pinfunction "BIN1_9") (pintype "input"))
    )
    (net (code "17") (name "/LF_RV") (class "Default")
      (node (ref "DS7") (pin "2") (pinfunction "K_2") (pintype "passive"))
      (node (ref "R_IR9") (pin "2") (pinfunction "2_2") (pintype "passive"))
      (node (ref "U1") (pin "10") (pinfunction "PC2/SPI2_MISO_10") (pintype "bidirectional"))
    )
    (net (code "18") (name "/LR_EM") (class "Default")
      (node (ref "Q1") (pin "1") (pinfunction "G_1") (pintype "passive"))
      (node (ref "R_IR1") (pin "2") (pinfunction "2_2") (pintype "passive"))
      (node (ref "U1") (pin "3") (pinfunction "PC14/OSC32_IN_3") (pintype "bidirectional"))
    )
    (net (code "19") (name "/L_RV") (class "Default")
      (node (ref "DS6") (pin "2") (pinfunction "K_2") (pintype "passive"))
      (node (ref "R_IR10") (pin "2") (pinfunction "2_2") (pintype "passive"))
      (node (ref "U1") (pin "8") (pinfunction "PC0_8") (pintype "bidirectional"))
    )
    (net (code "20") (name "/NetLabel24") (class "Default")
      (node (ref "U1") (pin "45") (pinfunction "PA12_45") (pintype "bidirectional+no_connect"))
    )
    (net (code "21") (name "/NetLabel27") (class "Default")
      (node (ref "U1") (pin "50") (pinfunction "PA15_50") (pintype "bidirectional+no_connect"))
    )
    (net (code "22") (name "/NetLabel44") (class "Default")
      (node (ref "U1") (pin "54") (pinfunction "PD2_54") (pintype "bidirectional+no_connect"))
    )
    (net (code "23") (name "/NetLabel48") (class "Default")
      (node (ref "U1") (pin "53") (pinfunction "PC12_53") (pintype "bidirectional+no_connect"))
    )
    (net (code "24") (name "/NetLabel80") (class "Default")
      (node (ref "U1") (pin "56") (pinfunction "PB4_56") (pintype "bidirectional+no_connect"))
    )
    (net (code "25") (name "/NetLabel85") (class "Default")
      (node (ref "U1") (pin "37") (pinfunction "PC6_37") (pintype "bidirectional+no_connect"))
    )
    (net (code "26") (name "/NetLabel86") (class "Default")
      (node (ref "U1") (pin "44") (pinfunction "PA11_44") (pintype "bidirectional+no_connect"))
    )
    (net (code "27") (name "/NetLabel90") (class "Default")
      (node (ref "U1") (pin "61") (pinfunction "PB8_61") (pintype "bidirectional+no_connect"))
    )
    (net (code "28") (name "/NetLabel91") (class "Default")
      (node (ref "U1") (pin "62") (pinfunction "PB9_62") (pintype "bidirectional+no_connect"))
    )
    (net (code "29") (name "/NetLabel92") (class "Default")
      (node (ref "U1") (pin "33") (pinfunction "PB12_33") (pintype "bidirectional+no_connect"))
    )
    (net (code "30") (name "/NetLabel93") (class "Default")
      (node (ref "U1") (pin "34") (pinfunction "PB13_34") (pintype "bidirectional+no_connect"))
    )
    (net (code "31") (name "/NetLabel94") (class "Default")
      (node (ref "U1") (pin "35") (pinfunction "PB14_35") (pintype "bidirectional+no_connect"))
    )
    (net (code "32") (name "/NetLabel95") (class "Default")
      (node (ref "U1") (pin "36") (pinfunction "PB15_36") (pintype "bidirectional+no_connect"))
    )
    (net (code "33") (name "/NetLabel96") (class "Default")
      (node (ref "U1") (pin "9") (pinfunction "PC1_9") (pintype "bidirectional+no_connect"))
    )
    (net (code "34") (name "/NetLabel97") (class "Default")
      (node (ref "U1") (pin "11") (pinfunction "PC3/SPI2_MOSI_11") (pintype "bidirectional+no_connect"))
    )
    (net (code "35") (name "/OUT1") (class "Default")
      (node (ref "J1") (pin "01") (pinfunction "01_01") (pintype "passive"))
      (node (ref "U5") (pin "4") (pinfunction "AOUT2_4") (pintype "tri_state"))
    )
    (net (code "36") (name "/OUT2") (class "Default")
      (node (ref "J1") (pin "02") (pinfunction "02_02") (pintype "passive"))
      (node (ref "U5") (pin "2") (pinfunction "AOUT1_2") (pintype "output"))
    )
    (net (code "37") (name "/OUT3") (class "Default")
      (node (ref "J2") (pin "01") (pinfunction "01_01") (pintype "passive"))
      (node (ref "U5") (pin "5") (pinfunction "BOUT2_5") (pintype "tri_state"))
    )
    (net (code "38") (name "/OUT4") (class "Default")
      (node (ref "J2") (pin "02") (pinfunction "02_02") (pintype "passive"))
      (node (ref "U5") (pin "7") (pinfunction "BOUT1_7") (pintype "tri_state"))
    )
    (net (code "39") (name "/OUT_A") (class "Default")
      (node (ref "J4_A") (pin "03") (pinfunction "03_03") (pintype "passive"))
      (node (ref "U_enA") (pin "3") (pinfunction "OUT_3") (pintype "passive"))
    )
    (net (code "40") (name "/OUT_B") (class "Default")
      (node (ref "J4_B") (pin "03") (pinfunction "03_03") (pintype "passive"))
      (node (ref "U_enB") (pin "3") (pinfunction "OUT_3") (pintype "passive"))
    )
    (net (code "41") (name "/OUT_enA") (class "Default")
      (node (ref "J3_A") (pin "03") (pinfunction "03_03") (pintype "passive"))
      (node (ref "U1") (pin "52") (pinfunction "PC11_52") (pintype "bidirectional"))
    )
    (net (code "42") (name "/OUT_enB") (class "Default")
      (node (ref "J3_B") (pin "03") (pinfunction "03_03") (pintype "passive"))
      (node (ref "U1") (pin "51") (pinfunction "PC10_51") (pintype "bidirectional"))
    )
    (net (code "43") (name "/PB2") (class "Default")
      (node (ref "R9") (pin "1") (pinfunction "1_1") (pintype "passive"))
      (node (ref "U1") (pin "28") (pinfunction "PB2/BOOT1_28") (pintype "bidirectional"))
    )
    (net (code "44") (name "/PushA") (class "Default")
      (node (ref "U_enA") (pin "5") (pinfunction "PUSH_5") (pintype "passive+no_connect"))
    )
    (net (code "45") (name "/PushB") (class "Default")
      (node (ref "U_enB") (pin "5") (pinfunction "PUSH_5") (pintype "passive+no_connect"))
    )
    (net (code "46") (name "/RF_RV") (class "Default")
      (node (ref "DS5") (pin "2") (pinfunction "K_2") (pintype "passive"))
      (node (ref "R_IR7") (pin "2") (pinfunction "2_2") (pintype "passive"))
      (node (ref "U1") (pin "38") (pinfunction "PC7_38") (pintype "bidirectional"))
    )
    (net (code "47") (name "/RX") (class "Default")
      (node (ref "P1") (pin "4") (pinfunction "4_4") (pintype "passive"))
      (node (ref "U1") (pin "43") (pinfunction "PA10_43") (pintype "bidirectional"))
    )
    (net (code "48") (name "/R_RV") (class "Default")
      (node (ref "DS8") (pin "2") (pinfunction "K_2") (pintype "passive"))
      (node (ref "R_IR8") (pin "2") (pinfunction "2_2") (pintype "passive"))
      (node (ref "U1") (pin "39") (pinfunction "PC8_39") (pintype "bidirectional"))
    )
    (net (code "49") (name "/SCL") (class "Default")
      (node (ref "J3") (pin "02") (pinfunction "02_02") (pintype "passive"))
      (node (ref "U1") (pin "58") (pinfunction "PB6_58") (pintype "bidirectional"))
    )
    (net (code "50") (name "/SCL_A") (class "Default")
      (node (ref "J4_A") (pin "02") (pinfunction "02_02") (pintype "passive"))
      (node (ref "R18") (pin "1") (pinfunction "1_1") (pintype "passive"))
      (node (ref "U_enA") (pin "7") (pinfunction "B_7") (pintype "passive"))
    )
    (net (code "51") (name "/SCL_B") (class "Default")
      (node (ref "J4_B") (pin "02") (pinfunction "02_02") (pintype "passive"))
      (node (ref "R16") (pin "1") (pinfunction "1_1") (pintype "passive"))
      (node (ref "U_enB") (pin "7") (pinfunction "B_7") (pintype "passive"))
    )
    (net (code "52") (name "/SCL_enA") (class "Default")
      (node (ref "J3_A") (pin "02") (pinfunction "02_02") (pintype "passive"))
      (node (ref "U1") (pin "41") (pinfunction "PA8_41") (pintype "bidirectional"))
    )
    (net (code "53") (name "/SCL_enB") (class "Default")
      (node (ref "J3_B") (pin "02") (pinfunction "02_02") (pintype "passive"))
      (node (ref "U1") (pin "29") (pinfunction "PB10_29") (pintype "bidirectional"))
    )
    (net (code "54") (name "/SDA") (class "Default")
      (node (ref "J3") (pin "03") (pinfunction "03_03") (pintype "passive"))
      (node (ref "U1") (pin "59") (pinfunction "PB7_59") (pintype "bidirectional"))
    )
    (net (code "55") (name "/SDA_A") (class "Default")
      (node (ref "J4_A") (pin "01") (pinfunction "01_01") (pintype "passive"))
      (node (ref "R19") (pin "1") (pinfunction "1_1") (pintype "passive"))
      (node (ref "U_enA") (pin "6") (pinfunction "A_6") (pintype "passive"))
    )
    (net (code "56") (name "/SDA_B") (class "Default")
      (node (ref "J4_B") (pin "01") (pinfunction "01_01") (pintype "passive"))
      (node (ref "R17") (pin "1") (pinfunction "1_1") (pintype "passive"))
      (node (ref "U_enB") (pin "6") (pinfunction "A_6") (pintype "passive"))
    )
    (net (code "57") (name "/SDA_enA") (class "Default")
      (node (ref "J3_A") (pin "01") (pinfunction "01_01") (pintype "passive"))
      (node (ref "U1") (pin "40") (pinfunction "PC9_40") (pintype "bidirectional"))
    )
    (net (code "58") (name "/SDA_enB") (class "Default")
      (node (ref "J3_B") (pin "01") (pinfunction "01_01") (pintype "passive"))
      (node (ref "U1") (pin "30") (pinfunction "PB11_30") (pintype "bidirectional"))
    )
    (net (code "59") (name "/SWCLK") (class "Default")
      (node (ref "P0") (pin "03") (pinfunction "03_03") (pintype "passive"))
      (node (ref "U1") (pin "49") (pinfunction "PA14/JTCK-SWCLK_49") (pintype "bidirectional"))
    )
    (net (code "60") (name "/SWDIO") (class "Default")
      (node (ref "P0") (pin "02") (pinfunction "02_02") (pintype "passive"))
      (node (ref "U1") (pin "46") (pinfunction "PA13/JMS-SWDIO_46") (pintype "bidirectional"))
    )
    (net (code "61") (name "/TX") (class "Default")
      (node (ref "P1") (pin "3") (pinfunction "3_3") (pintype "passive"))
      (node (ref "U1") (pin "42") (pinfunction "PA9_42") (pintype "bidirectional"))
    )
    (net (code "62") (name "/V_inA") (class "Default")
      (node (ref "C_enA") (pin "1") (pinfunction "1_1") (pintype "passive"))
      (node (ref "J4_A") (pin "05") (pinfunction "05_05") (pintype "passive"))
      (node (ref "R18") (pin "2") (pinfunction "2_2") (pintype "passive"))
      (node (ref "R19") (pin "2") (pinfunction "2_2") (pintype "passive"))
      (node (ref "U_enA") (pin "1") (pinfunction "VDD_1") (pintype "passive"))
      (node (ref "U_enA") (pin "2") (pinfunction "MODE_2") (pintype "passive"))
      (node (ref "U_enA") (pin "8") (pinfunction "Z_8") (pintype "passive"))
    )
    (net (code "63") (name "/V_inB") (class "Default")
      (node (ref "C_enB") (pin "1") (pinfunction "1_1") (pintype "passive"))
      (node (ref "J4_B") (pin "05") (pinfunction "05_05") (pintype "passive"))
      (node (ref "R16") (pin "2") (pinfunction "2_2") (pintype "passive"))
      (node (ref "R17") (pin "2") (pinfunction "2_2") (pintype "passive"))
      (node (ref "U_enB") (pin "1") (pinfunction "VDD_1") (pintype "passive"))
      (node (ref "U_enB") (pin "2") (pinfunction "MODE_2") (pintype "passive"))
      (node (ref "U_enB") (pin "8") (pinfunction "Z_8") (pintype "passive"))
    )
    (net (code "64") (name "GND") (class "Default")
      (node (ref "C1") (pin "2") (pinfunction "2_2") (pintype "passive"))
      (node (ref "C10") (pin "2") (pinfunction "2_2") (pintype "passive"))
      (node (ref "C11") (pin "1") (pinfunction "C_1") (pintype "passive"))
      (node (ref "C12") (pin "2") (pinfunction "2_2") (pintype "passive"))
      (node (ref "C13") (pin "2") (pinfunction "2_2") (pintype "passive"))
      (node (ref "C16") (pin "2") (pinfunction "2_2") (pintype "passive"))
      (node (ref "C17") (pin "2") (pinfunction "2_2") (pintype "passive"))
      (node (ref "C18") (pin "2") (pinfunction "2_2") (pintype "passive"))
      (node (ref "C19") (pin "1") (pinfunction "C_1") (pintype "passive"))
      (node (ref "C2") (pin "2") (pinfunction "2_2") (pintype "passive"))
      (node (ref "C21") (pin "2") (pinfunction "2_2") (pintype "passive"))
      (node (ref "C22") (pin "2") (pinfunction "2_2") (pintype "passive"))
      (node (ref "C23") (pin "2") (pinfunction "2_2") (pintype "passive"))
      (node (ref "C24") (pin "2") (pinfunction "2_2") (pintype "passive"))
      (node (ref "C27") (pin "1") (pinfunction "C_1") (pintype "passive"))
      (node (ref "C3") (pin "1") (pinfunction "1_1") (pintype "passive"))
      (node (ref "C4") (pin "2") (pinfunction "2_2") (pintype "passive"))
      (node (ref "C5") (pin "2") (pinfunction "2_2") (pintype "passive"))
      (node (ref "C6") (pin "2") (pinfunction "2_2") (pintype "passive"))
      (node (ref "C7") (pin "2") (pinfunction "2_2") (pintype "passive"))
      (node (ref "C8") (pin "2") (pinfunction "2_2") (pintype "passive"))
      (node (ref "C9") (pin "2") (pinfunction "2_2") (pintype "passive"))
      (node (ref "C_IR1") (pin "2") (pinfunction "2_2") (pintype "passive"))
      (node (ref "C_IR2") (pin "1") (pinfunction "1_1") (pintype "passive"))
      (node (ref "C_IR3") (pin "1") (pinfunction "1_1") (pintype "passive"))
      (node (ref "C_IR4") (pin "2") (pinfunction "2_2") (pintype "passive"))
      (node (ref "D1") (pin "1") (pinfunction "C_1") (pintype "passive"))
      (node (ref "D10") (pin "1") (pinfunction "C_1") (pintype "passive"))
      (node (ref "D11") (pin "1") (pinfunction "C_1") (pintype "passive"))
      (node (ref "D12") (pin "1") (pinfunction "C_1") (pintype "passive"))
      (node (ref "D13") (pin "1") (pinfunction "C_1") (pintype "passive"))
      (node (ref "D3") (pin "1") (pinfunction "C_1") (pintype "passive"))
      (node (ref "D5") (pin "1") (pinfunction "C_1") (pintype "passive"))
      (node (ref "D6") (pin "1") (pinfunction "C_1") (pintype "passive"))
      (node (ref "D7") (pin "1") (pinfunction "C_1") (pintype "passive"))
      (node (ref "D8") (pin "1") (pinfunction "C_1") (pintype "passive"))
      (node (ref "D9") (pin "1") (pinfunction "C_1") (pintype "passive"))
      (node (ref "J3") (pin "04") (pinfunction "04_04") (pintype "passive"))
      (node (ref "J3_A") (pin "04") (pinfunction "04_04") (pintype "passive"))
      (node (ref "J3_B") (pin "04") (pinfunction "04_04") (pintype "passive"))
      (node (ref "P0") (pin "04") (pinfunction "04_04") (pintype "passive"))
      (node (ref "P1") (pin "2") (pinfunction "2_2") (pintype "passive"))
      (node (ref "P3") (pin "2") (pinfunction "2_2") (pintype "passive"))
      (node (ref "Q1") (pin "2") (pinfunction "S_2") (pintype "passive"))
      (node (ref "Q2") (pin "2") (pinfunction "S_2") (pintype "passive"))
      (node (ref "Q3") (pin "2") (pinfunction "S_2") (pintype "passive"))
      (node (ref "R12") (pin "2") (pinfunction "2_2") (pintype "passive"))
      (node (ref "R5") (pin "1") (pinfunction "1_1") (pintype "passive"))
      (node (ref "R7") (pin "1") (pinfunction "1_1") (pintype "passive"))
      (node (ref "R9") (pin "2") (pinfunction "2_2") (pintype "passive"))
      (node (ref "RST") (pin "2") (pinfunction "2_2") (pintype "passive"))
      (node (ref "R_BT") (pin "1") (pinfunction "1_1") (pintype "passive"))
      (node (ref "R_BT0_2") (pin "1") (pinfunction "1_1") (pintype "passive"))
      (node (ref "R_BUZZ") (pin "1") (pinfunction "1_1") (pintype "passive"))
      (node (ref "R_IR1") (pin "1") (pinfunction "1_1") (pintype "passive"))
      (node (ref "R_IR10") (pin "1") (pinfunction "1_1") (pintype "passive"))
      (node (ref "R_IR2") (pin "1") (pinfunction "1_1") (pintype "passive"))
      (node (ref "R_IR7") (pin "1") (pinfunction "1_1") (pintype "passive"))
      (node (ref "R_IR8") (pin "1") (pinfunction "1_1") (pintype "passive"))
      (node (ref "R_IR9") (pin "1") (pinfunction "1_1") (pintype "passive"))
      (node (ref "U1") (pin "12") (pinfunction "VSSA_12") (pintype "power_in"))
      (node (ref "U1") (pin "18") (pinfunction "VSS_18") (pintype "power_in"))
      (node (ref "U1") (pin "63") (pinfunction "VSS_63") (pintype "power_in"))
      (node (ref "U2") (pin "1") (pinfunction "GND_1") (pintype "power_in"))
      (node (ref "U3") (pin "4") (pinfunction "GND_4") (pintype "power_in"))
      (node (ref "U5") (pin "13") (pinfunction "GND_13") (pintype "power_in"))
      (node (ref "U5") (pin "17") (pinfunction "GND_17") (pintype "power_in"))
      (node (ref "U6") (pin "1") (pinfunction "GND_1") (pintype "power_in"))
    )
    (net (code "65") (name "GND_inA") (class "Default")
      (node (ref "C_enA") (pin "2") (pinfunction "2_2") (pintype "passive"))
      (node (ref "J4_A") (pin "04") (pinfunction "04_04") (pintype "passive"))
      (node (ref "U_enA") (pin "4") (pinfunction "GND_4") (pintype "passive"))
    )
    (net (code "66") (name "GND_inB") (class "Default")
      (node (ref "C_enB") (pin "2") (pinfunction "2_2") (pintype "passive"))
      (node (ref "J4_B") (pin "04") (pinfunction "04_04") (pintype "passive"))
      (node (ref "U_enB") (pin "4") (pinfunction "GND_4") (pintype "passive"))
    )
    (net (code "67") (name "Net-(BOOT0-Pad1)") (class "Default")
      (node (ref "BOOT0") (pin "1") (pinfunction "1_1") (pintype "passive"))
      (node (ref "R_BT0_1") (pin "2") (pinfunction "2_2") (pintype "passive"))
      (node (ref "R_BT0_2") (pin "2") (pinfunction "2_2") (pintype "passive"))
    )
    (net (code "68") (name "Net-(C11-A)") (class "Default")
      (node (ref "C11") (pin "2") (pinfunction "A_2") (pintype "passive"))
      (node (ref "U1") (pin "31") (pinfunction "VCAP_1_31") (pintype "power_in"))
    )
    (net (code "69") (name "Net-(C14-Pad2)") (class "Default")
      (node (ref "C14") (pin "2") (pinfunction "2_2") (pintype "passive"))
      (node (ref "R5") (pin "2") (pinfunction "2_2") (pintype "passive"))
    )
    (net (code "70") (name "Net-(C27-A)") (class "Default")
      (node (ref "C27") (pin "2") (pinfunction "A_2") (pintype "passive"))
      (node (ref "U1") (pin "47") (pinfunction "VCAP_2_47") (pintype "power_in"))
    )
    (net (code "71") (name "Net-(D1-A)") (class "Default")
      (node (ref "D1") (pin "2") (pinfunction "A_2") (pintype "passive"))
      (node (ref "R3") (pin "2") (pinfunction "2_2") (pintype "passive"))
    )
    (net (code "72") (name "Net-(D3-A)") (class "Default")
      (node (ref "D3") (pin "2") (pinfunction "A_2") (pintype "passive"))
      (node (ref "R10") (pin "2") (pinfunction "2_2") (pintype "passive"))
    )
    (net (code "73") (name "Net-(D4-A)") (class "Default")
      (node (ref "D4") (pin "2") (pinfunction "A_2") (pintype "passive"))
      (node (ref "LS1") (pin "1") (pinfunction "C_1") (pintype "passive"))
      (node (ref "Q3") (pin "3") (pinfunction "D_3") (pintype "passive"))
    )
    (net (code "74") (name "Net-(D5-A)") (class "Default")
      (node (ref "D5") (pin "2") (pinfunction "A_2") (pintype "passive"))
      (node (ref "DBL_1") (pin "1") (pinfunction "1_1") (pintype "passive"))
    )
    (net (code "75") (name "Net-(D6-A)") (class "Default")
      (node (ref "D6") (pin "2") (pinfunction "A_2") (pintype "passive"))
      (node (ref "DBL_2") (pin "1") (pinfunction "1_1") (pintype "passive"))
    )
    (net (code "76") (name "Net-(D7-A)") (class "Default")
      (node (ref "D7") (pin "2") (pinfunction "A_2") (pintype "passive"))
      (node (ref "DBL_3") (pin "1") (pinfunction "1_1") (pintype "passive"))
    )
    (net (code "77") (name "Net-(D8-A)") (class "Default")
      (node (ref "D8") (pin "2") (pinfunction "A_2") (pintype "passive"))
      (node (ref "DBL_4") (pin "1") (pinfunction "1_1") (pintype "passive"))
    )
    (net (code "78") (name "Net-(D9-A)") (class "Default")
      (node (ref "D9") (pin "2") (pinfunction "A_2") (pintype "passive"))
      (node (ref "DBL_5") (pin "1") (pinfunction "1_1") (pintype "passive"))
    )
    (net (code "79") (name "Net-(D10-A)") (class "Default")
      (node (ref "D10") (pin "2") (pinfunction "A_2") (pintype "passive"))
      (node (ref "DBL_6") (pin "1") (pinfunction "1_1") (pintype "passive"))
    )
    (net (code "80") (name "Net-(D11-A)") (class "Default")
      (node (ref "D11") (pin "2") (pinfunction "A_2") (pintype "passive"))
      (node (ref "DBL_7") (pin "1") (pinfunction "1_1") (pintype "passive"))
    )
    (net (code "81") (name "Net-(D12-A)") (class "Default")
      (node (ref "D12") (pin "2") (pinfunction "A_2") (pintype "passive"))
      (node (ref "DBL_8") (pin "1") (pinfunction "1_1") (pintype "passive"))
    )
    (net (code "82") (name "Net-(D13-A)") (class "Default")
      (node (ref "D13") (pin "2") (pinfunction "A_2") (pintype "passive"))
      (node (ref "R13") (pin "2") (pinfunction "2_2") (pintype "passive"))
    )
    (net (code "83") (name "Net-(DS1-C)") (class "Default")
      (node (ref "DS1") (pin "1") (pinfunction "C_1") (pintype "passive"))
      (node (ref "R_IR3") (pin "2") (pinfunction "2_2") (pintype "passive"))
    )
    (net (code "84") (name "Net-(DS2-C)") (class "Default")
      (node (ref "DS2") (pin "1") (pinfunction "C_1") (pintype "passive"))
      (node (ref "R_IR4") (pin "2") (pinfunction "2_2") (pintype "passive"))
    )
    (net (code "85") (name "Net-(DS3-C)") (class "Default")
      (node (ref "DS3") (pin "1") (pinfunction "C_1") (pintype "passive"))
      (node (ref "R_IR6") (pin "2") (pinfunction "2_2") (pintype "passive"))
    )
    (net (code "86") (name "Net-(DS4-C)") (class "Default")
      (node (ref "DS4") (pin "1") (pinfunction "C_1") (pintype "passive"))
      (node (ref "R_IR5") (pin "2") (pinfunction "2_2") (pintype "passive"))
    )
    (net (code "87") (name "Net-(Q1-D)") (class "Default")
      (node (ref "Q1") (pin "3") (pinfunction "D_3") (pintype "passive"))
      (node (ref "R_IR4") (pin "1") (pinfunction "1_1") (pintype "passive"))
      (node (ref "R_IR6") (pin "1") (pinfunction "1_1") (pintype "passive"))
    )
    (net (code "88") (name "Net-(Q2-D)") (class "Default")
      (node (ref "Q2") (pin "3") (pinfunction "D_3") (pintype "passive"))
      (node (ref "R_IR3") (pin "1") (pinfunction "1_1") (pintype "passive"))
      (node (ref "R_IR5") (pin "1") (pinfunction "1_1") (pintype "passive"))
    )
    (net (code "89") (name "Net-(SW0-COM)") (class "Default")
      (node (ref "P3") (pin "1") (pinfunction "1_1") (pintype "passive"))
      (node (ref "SW0") (pin "2") (pinfunction "COM_2") (pintype "passive"))
    )
    (net (code "90") (name "Net-(U1-NRST)") (class "Default")
      (node (ref "C3") (pin "2") (pinfunction "2_2") (pintype "passive"))
      (node (ref "R2") (pin "2") (pinfunction "2_2") (pintype "passive"))
      (node (ref "RST") (pin "1") (pinfunction "1_1") (pintype "passive"))
      (node (ref "U1") (pin "7") (pinfunction "NRST_7") (pintype "bidirectional"))
    )
    (net (code "91") (name "Net-(U1-PH0{slash}OSC_IN)") (class "Default")
      (node (ref "C1") (pin "1") (pinfunction "1_1") (pintype "passive"))
      (node (ref "U1") (pin "5") (pinfunction "PH0/OSC_IN_5") (pintype "bidirectional"))
      (node (ref "Y1") (pin "2") (pinfunction "2_2") (pintype "passive"))
    )
    (net (code "92") (name "Net-(U1-PH1{slash}OSC_OUT)") (class "Default")
      (node (ref "C2") (pin "1") (pinfunction "1_1") (pintype "passive"))
      (node (ref "U1") (pin "6") (pinfunction "PH1/OSC_OUT_6") (pintype "bidirectional"))
      (node (ref "Y1") (pin "1") (pinfunction "1_1") (pintype "passive"))
    )
    (net (code "93") (name "Net-(U3-BS)") (class "Default")
      (node (ref "C15") (pin "1") (pinfunction "1_1") (pintype "passive"))
      (node (ref "U3") (pin "1") (pinfunction "BS_1") (pintype "passive"))
    )
    (net (code "94") (name "Net-(U3-COMP)") (class "Default")
      (node (ref "C14") (pin "1") (pinfunction "1_1") (pintype "passive"))
      (node (ref "U3") (pin "6") (pinfunction "COMP_6") (pintype "passive"))
    )
    (net (code "95") (name "Net-(U3-EN)") (class "Default")
      (node (ref "3") (pin "2") (pinfunction "2_2") (pintype "passive"))
      (node (ref "U3") (pin "7") (pinfunction "EN_7") (pintype "input"))
    )
    (net (code "96") (name "Net-(U3-FB)") (class "Default")
      (node (ref "R7") (pin "2") (pinfunction "2_2") (pintype "passive"))
      (node (ref "R8") (pin "2") (pinfunction "2_2") (pintype "passive"))
      (node (ref "U3") (pin "5") (pinfunction "FB_5") (pintype "input"))
    )
    (net (code "97") (name "Net-(U3-SS)") (class "Default")
      (node (ref "C13") (pin "1") (pinfunction "1_1") (pintype "passive"))
      (node (ref "U3") (pin "8") (pinfunction "SS_8") (pintype "passive"))
    )
    (net (code "98") (name "Net-(U3-SW)") (class "Default")
      (node (ref "C15") (pin "2") (pinfunction "2_2") (pintype "passive"))
      (node (ref "L3") (pin "1") (pinfunction "1_1") (pintype "passive"))
      (node (ref "U3") (pin "3") (pinfunction "SW_3") (pintype "output"))
    )
    (net (code "99") (name "Net-(U5-AISEN)") (class "Default")
      (node (ref "R12") (pin "1") (pinfunction "1_1") (pintype "passive"))
      (node (ref "U5") (pin "3") (pinfunction "AISEN_3") (pintype "input"))
      (node (ref "U5") (pin "6") (pinfunction "BISEN_6") (pintype "input"))
    )
    (net (code "100") (name "Net-(U5-VCP)") (class "Default")
      (node (ref "C20") (pin "2") (pinfunction "2_2") (pintype "passive"))
      (node (ref "U5") (pin "11") (pinfunction "VCP_11") (pintype "passive"))
    )
    (net (code "101") (name "Net-(U5-VINT)") (class "Default")
      (node (ref "C21") (pin "1") (pinfunction "1_1") (pintype "passive"))
      (node (ref "U5") (pin "14") (pinfunction "VINT_14") (pintype "power_in"))
    )
    (net (code "102") (name "Net-(U5-~{SLEEP})") (class "Default")
      (node (ref "R11") (pin "2") (pinfunction "2_2") (pintype "passive"))
      (node (ref "U5") (pin "1") (pinfunction "~{SLEEP}_1") (pintype "input"))
    )
    (net (code "103") (name "V33") (class "Default")
      (node (ref "BOOT0") (pin "2") (pinfunction "2_2") (pintype "passive"))
      (node (ref "C24") (pin "1") (pinfunction "1_1") (pintype "passive"))
      (node (ref "C_DB") (pin "1") (pinfunction "1_1") (pintype "passive"))
      (node (ref "C_IR1") (pin "1") (pinfunction "1_1") (pintype "passive"))
      (node (ref "C_IR2") (pin "2") (pinfunction "2_2") (pintype "passive"))
      (node (ref "C_IR3") (pin "2") (pinfunction "2_2") (pintype "passive"))
      (node (ref "C_IR4") (pin "1") (pinfunction "1_1") (pintype "passive"))
      (node (ref "D4") (pin "1") (pinfunction "C_1") (pintype "passive"))
      (node (ref "DEBUG") (pin "2") (pinfunction "2_2") (pintype "passive"))
      (node (ref "DS1") (pin "2") (pinfunction "A_2") (pintype "passive"))
      (node (ref "DS2") (pin "2") (pinfunction "A_2") (pintype "passive"))
      (node (ref "DS3") (pin "2") (pinfunction "A_2") (pintype "passive"))
      (node (ref "DS4") (pin "2") (pinfunction "A_2") (pintype "passive"))
      (node (ref "DS5") (pin "1") (pinfunction "A_1") (pintype "passive"))
      (node (ref "DS6") (pin "1") (pinfunction "A_1") (pintype "passive"))
      (node (ref "DS7") (pin "1") (pinfunction "A_1") (pintype "passive"))
      (node (ref "DS8") (pin "1") (pinfunction "A_1") (pintype "passive"))
      (node (ref "J3") (pin "01") (pinfunction "01_01") (pintype "passive"))
      (node (ref "J3_A") (pin "05") (pinfunction "05_05") (pintype "passive"))
      (node (ref "J3_B") (pin "05") (pinfunction "05_05") (pintype "passive"))
      (node (ref "LS1") (pin "2") (pinfunction "A_2") (pintype "passive"))
      (node (ref "R13") (pin "1") (pinfunction "1_1") (pintype "passive"))
      (node (ref "U6") (pin "2") (pinfunction "OUT_2") (pintype "power_in"))
      (node (ref "U6") (pin "4") (pinfunction "TAB_4") (pintype "power_in"))
    )
    (net (code "104") (name "VDD33") (class "Default")
      (node (ref "C4") (pin "1") (pinfunction "1_1") (pintype "passive"))
      (node (ref "C5") (pin "1") (pinfunction "1_1") (pintype "passive"))
      (node (ref "C6") (pin "1") (pinfunction "1_1") (pintype "passive"))
      (node (ref "C7") (pin "1") (pinfunction "1_1") (pintype "passive"))
      (node (ref "C8") (pin "1") (pinfunction "1_1") (pintype "passive"))
      (node (ref "C9") (pin "1") (pinfunction "1_1") (pintype "passive"))
      (node (ref "L1") (pin "1") (pinfunction "1_1") (pintype "passive"))
      (node (ref "P4") (pin "2") (pinfunction "2_2") (pintype "passive"))
      (node (ref "R2") (pin "1") (pinfunction "1_1") (pintype "passive"))
      (node (ref "R3") (pin "1") (pinfunction "1_1") (pintype "passive"))
      (node (ref "U1") (pin "1") (pinfunction "VBAT_1") (pintype "power_in"))
      (node (ref "U1") (pin "19") (pinfunction "VDD_19") (pintype "power_in"))
      (node (ref "U1") (pin "32") (pinfunction "VDD_32") (pintype "power_in"))
      (node (ref "U1") (pin "48") (pinfunction "VDD_48") (pintype "power_in"))
      (node (ref "U1") (pin "64") (pinfunction "VDD_64") (pintype "power_in"))
    )
    (net (code "105") (name "VDD33_OUT") (class "Default")
      (node (ref "C18") (pin "1") (pinfunction "1_1") (pintype "passive"))
      (node (ref "P4") (pin "1") (pinfunction "1_1") (pintype "passive"))
      (node (ref "U2") (pin "2") (pinfunction "OUT_2") (pintype "power_in"))
      (node (ref "U2") (pin "4") (pinfunction "TAB_4") (pintype "power_in"))
    )
    (net (code "106") (name "VDDA") (class "Default")
      (node (ref "C10") (pin "1") (pinfunction "1_1") (pintype "passive"))
      (node (ref "C22") (pin "1") (pinfunction "1_1") (pintype "passive"))
      (node (ref "L1") (pin "2") (pinfunction "2_2") (pintype "passive"))
      (node (ref "U1") (pin "13") (pinfunction "VDDA_13") (pintype "power_in"))
    )
    (net (code "107") (name "VIN74") (class "Default")
      (node (ref "3") (pin "1") (pinfunction "1_1") (pintype "passive"))
      (node (ref "C12") (pin "1") (pinfunction "1_1") (pintype "passive"))
      (node (ref "SW0") (pin "3") (pinfunction "3_3") (pintype "passive"))
      (node (ref "U3") (pin "2") (pinfunction "IN_2") (pintype "input"))
    )
    (net (code "108") (name "VOUT5") (class "Default")
      (node (ref "C16") (pin "1") (pinfunction "1_1") (pintype "passive"))
      (node (ref "C17") (pin "1") (pinfunction "1_1") (pintype "passive"))
      (node (ref "C19") (pin "2") (pinfunction "A_2") (pintype "passive"))
      (node (ref "C20") (pin "1") (pinfunction "1_1") (pintype "passive"))
      (node (ref "C23") (pin "1") (pinfunction "1_1") (pintype "passive"))
      (node (ref "L3") (pin "2") (pinfunction "2_2") (pintype "passive"))
      (node (ref "P1") (pin "1") (pinfunction "1_1") (pintype "passive"))
      (node (ref "R10") (pin "1") (pinfunction "1_1") (pintype "passive"))
      (node (ref "R11") (pin "1") (pinfunction "1_1") (pintype "passive"))
      (node (ref "R8") (pin "1") (pinfunction "1_1") (pintype "passive"))
      (node (ref "U2") (pin "3") (pinfunction "IN_3") (pintype "power_in"))
      (node (ref "U5") (pin "12") (pinfunction "VM_12") (pintype "power_in"))
      (node (ref "U6") (pin "3") (pinfunction "IN_3") (pintype "power_in"))
    )
    (net (code "109") (name "unconnected-(P0-Pad01)") (class "Default")
      (node (ref "P0") (pin "01") (pinfunction "01_01") (pintype "passive+no_connect"))
    )
    (net (code "110") (name "unconnected-(P4-Pad3)") (class "Default")
      (node (ref "P4") (pin "3") (pinfunction "3_3") (pintype "passive+no_connect"))
    )
    (net (code "111") (name "unconnected-(P4-Pad4)") (class "Default")
      (node (ref "P4") (pin "4") (pinfunction "4_4") (pintype "passive+no_connect"))
    )
    (net (code "112") (name "unconnected-(SW0-Pad1)") (class "Default")
      (node (ref "SW0") (pin "1") (pinfunction "1_1") (pintype "passive+no_connect"))
    )
    (net (code "113") (name "unconnected-(U1-PB3-Pad55)") (class "Default")
      (node (ref "U1") (pin "55") (pinfunction "PB3_55") (pintype "bidirectional"))
    )
    (net (code "114") (name "unconnected-(U3-EP-Pad9)") (class "Default")
      (node (ref "U3") (pin "9") (pinfunction "EP_9") (pintype "power_in+no_connect"))
    )
    (net (code "115") (name "unconnected-(U5-~{FAULT}-Pad8)") (class "Default")
      (node (ref "U5") (pin "8") (pinfunction "~{FAULT}_8") (pintype "open_collector"))
    )
  )
)
